# keyboard.net
KiCad netlist of a schematic drawn in EAGLE
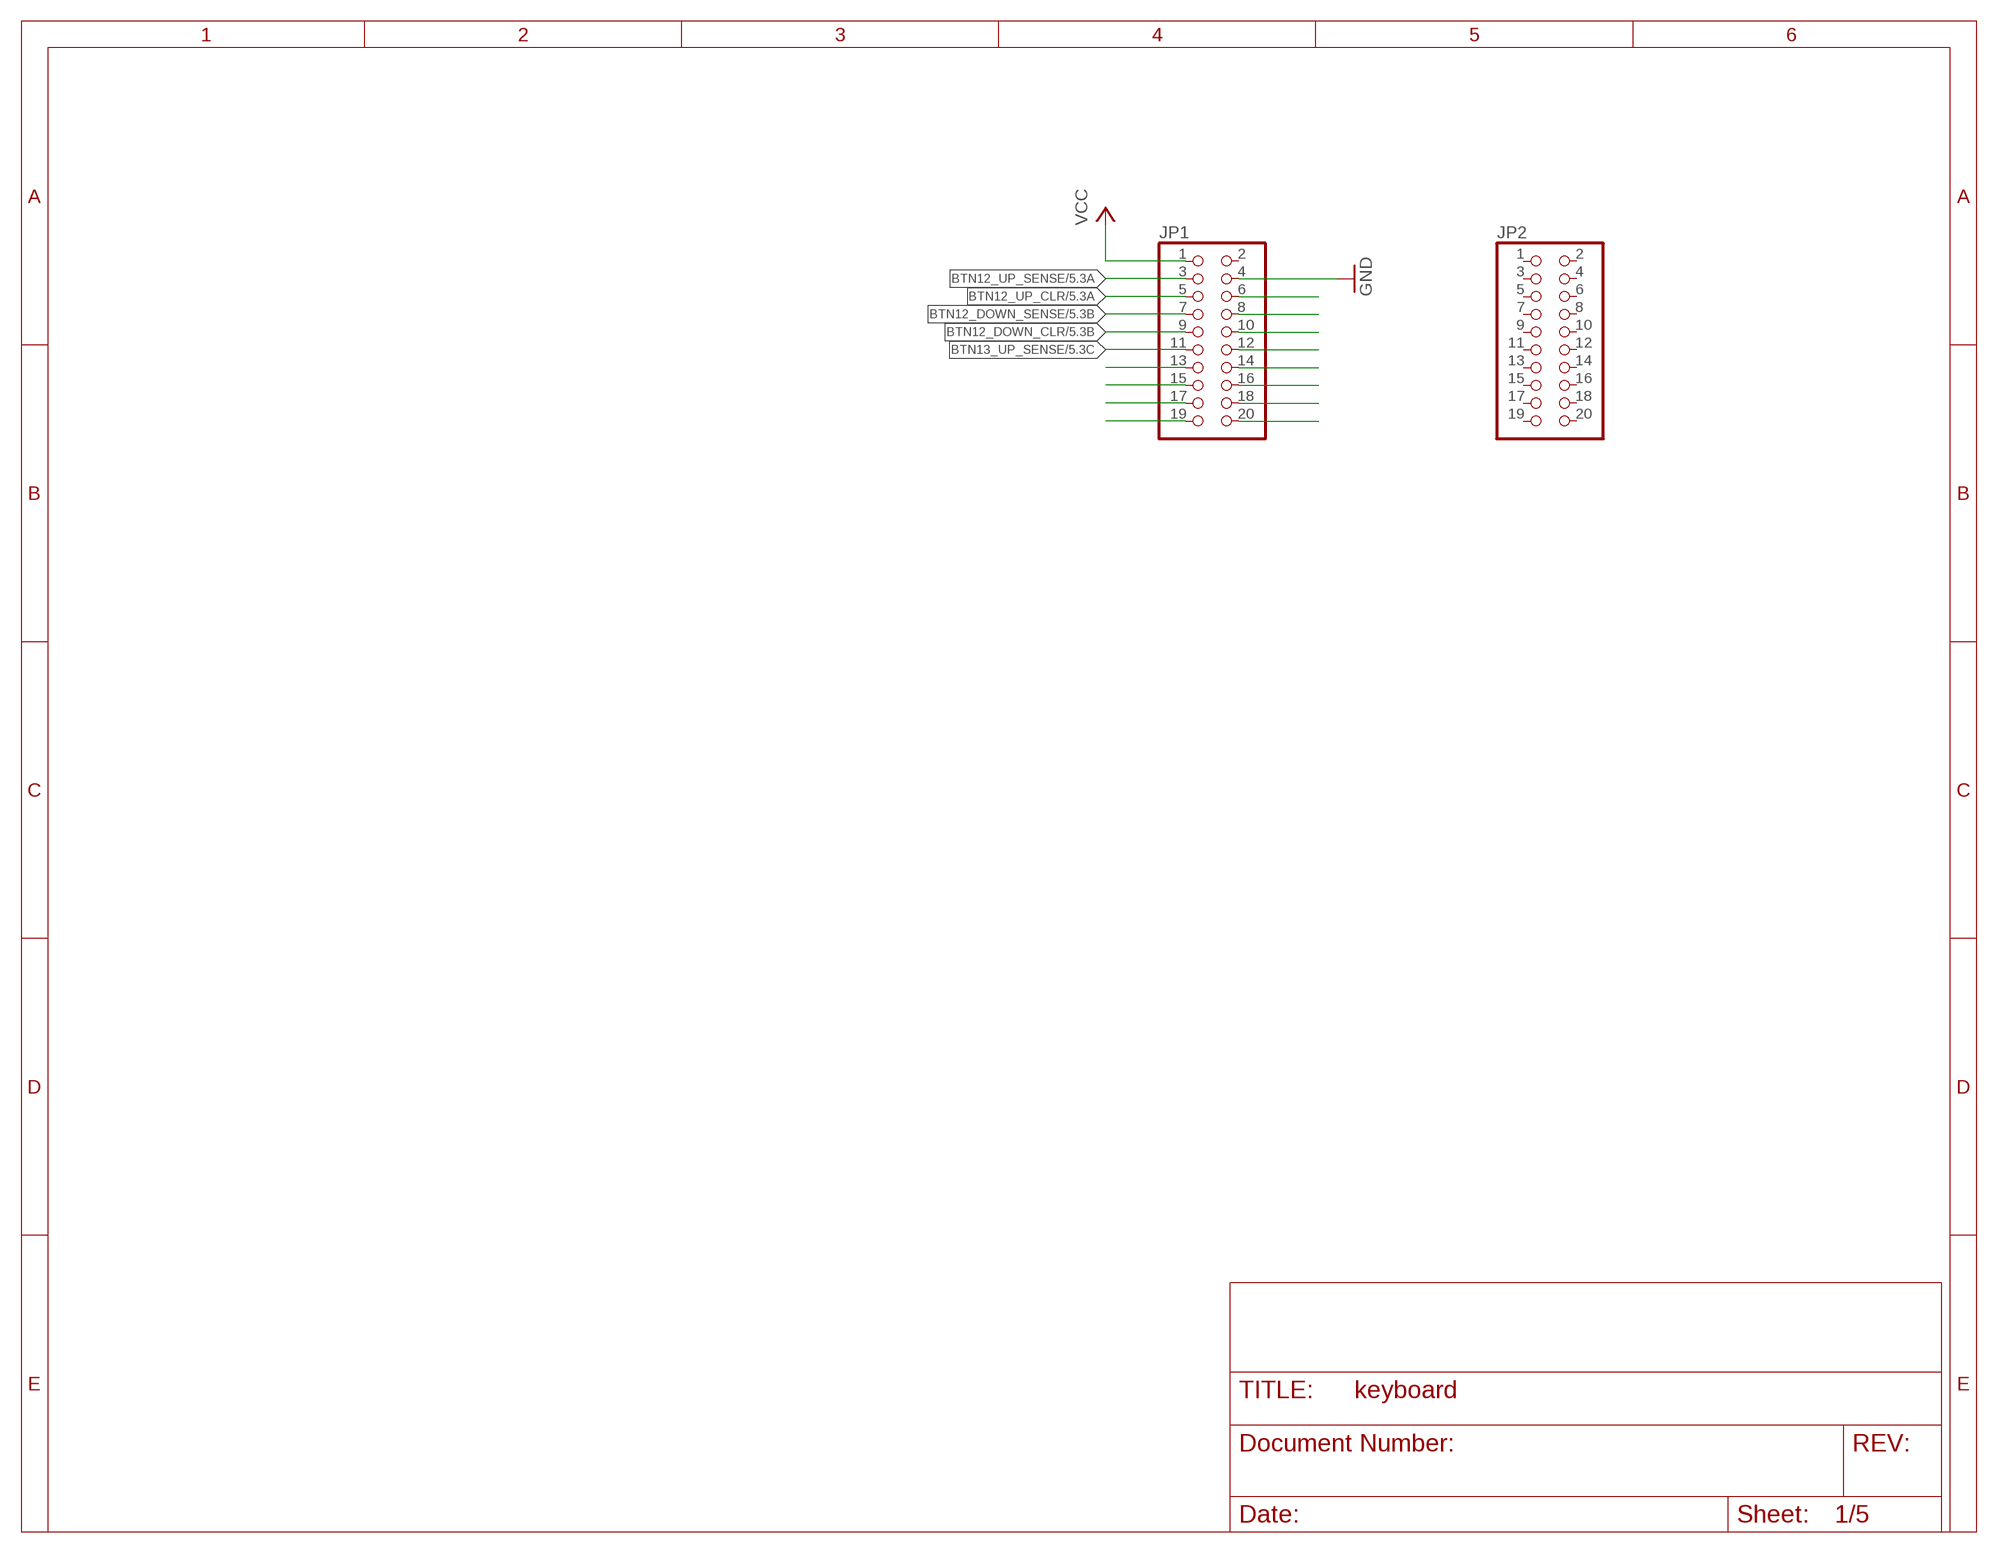
[diagram p0: schematic, sheet 1]
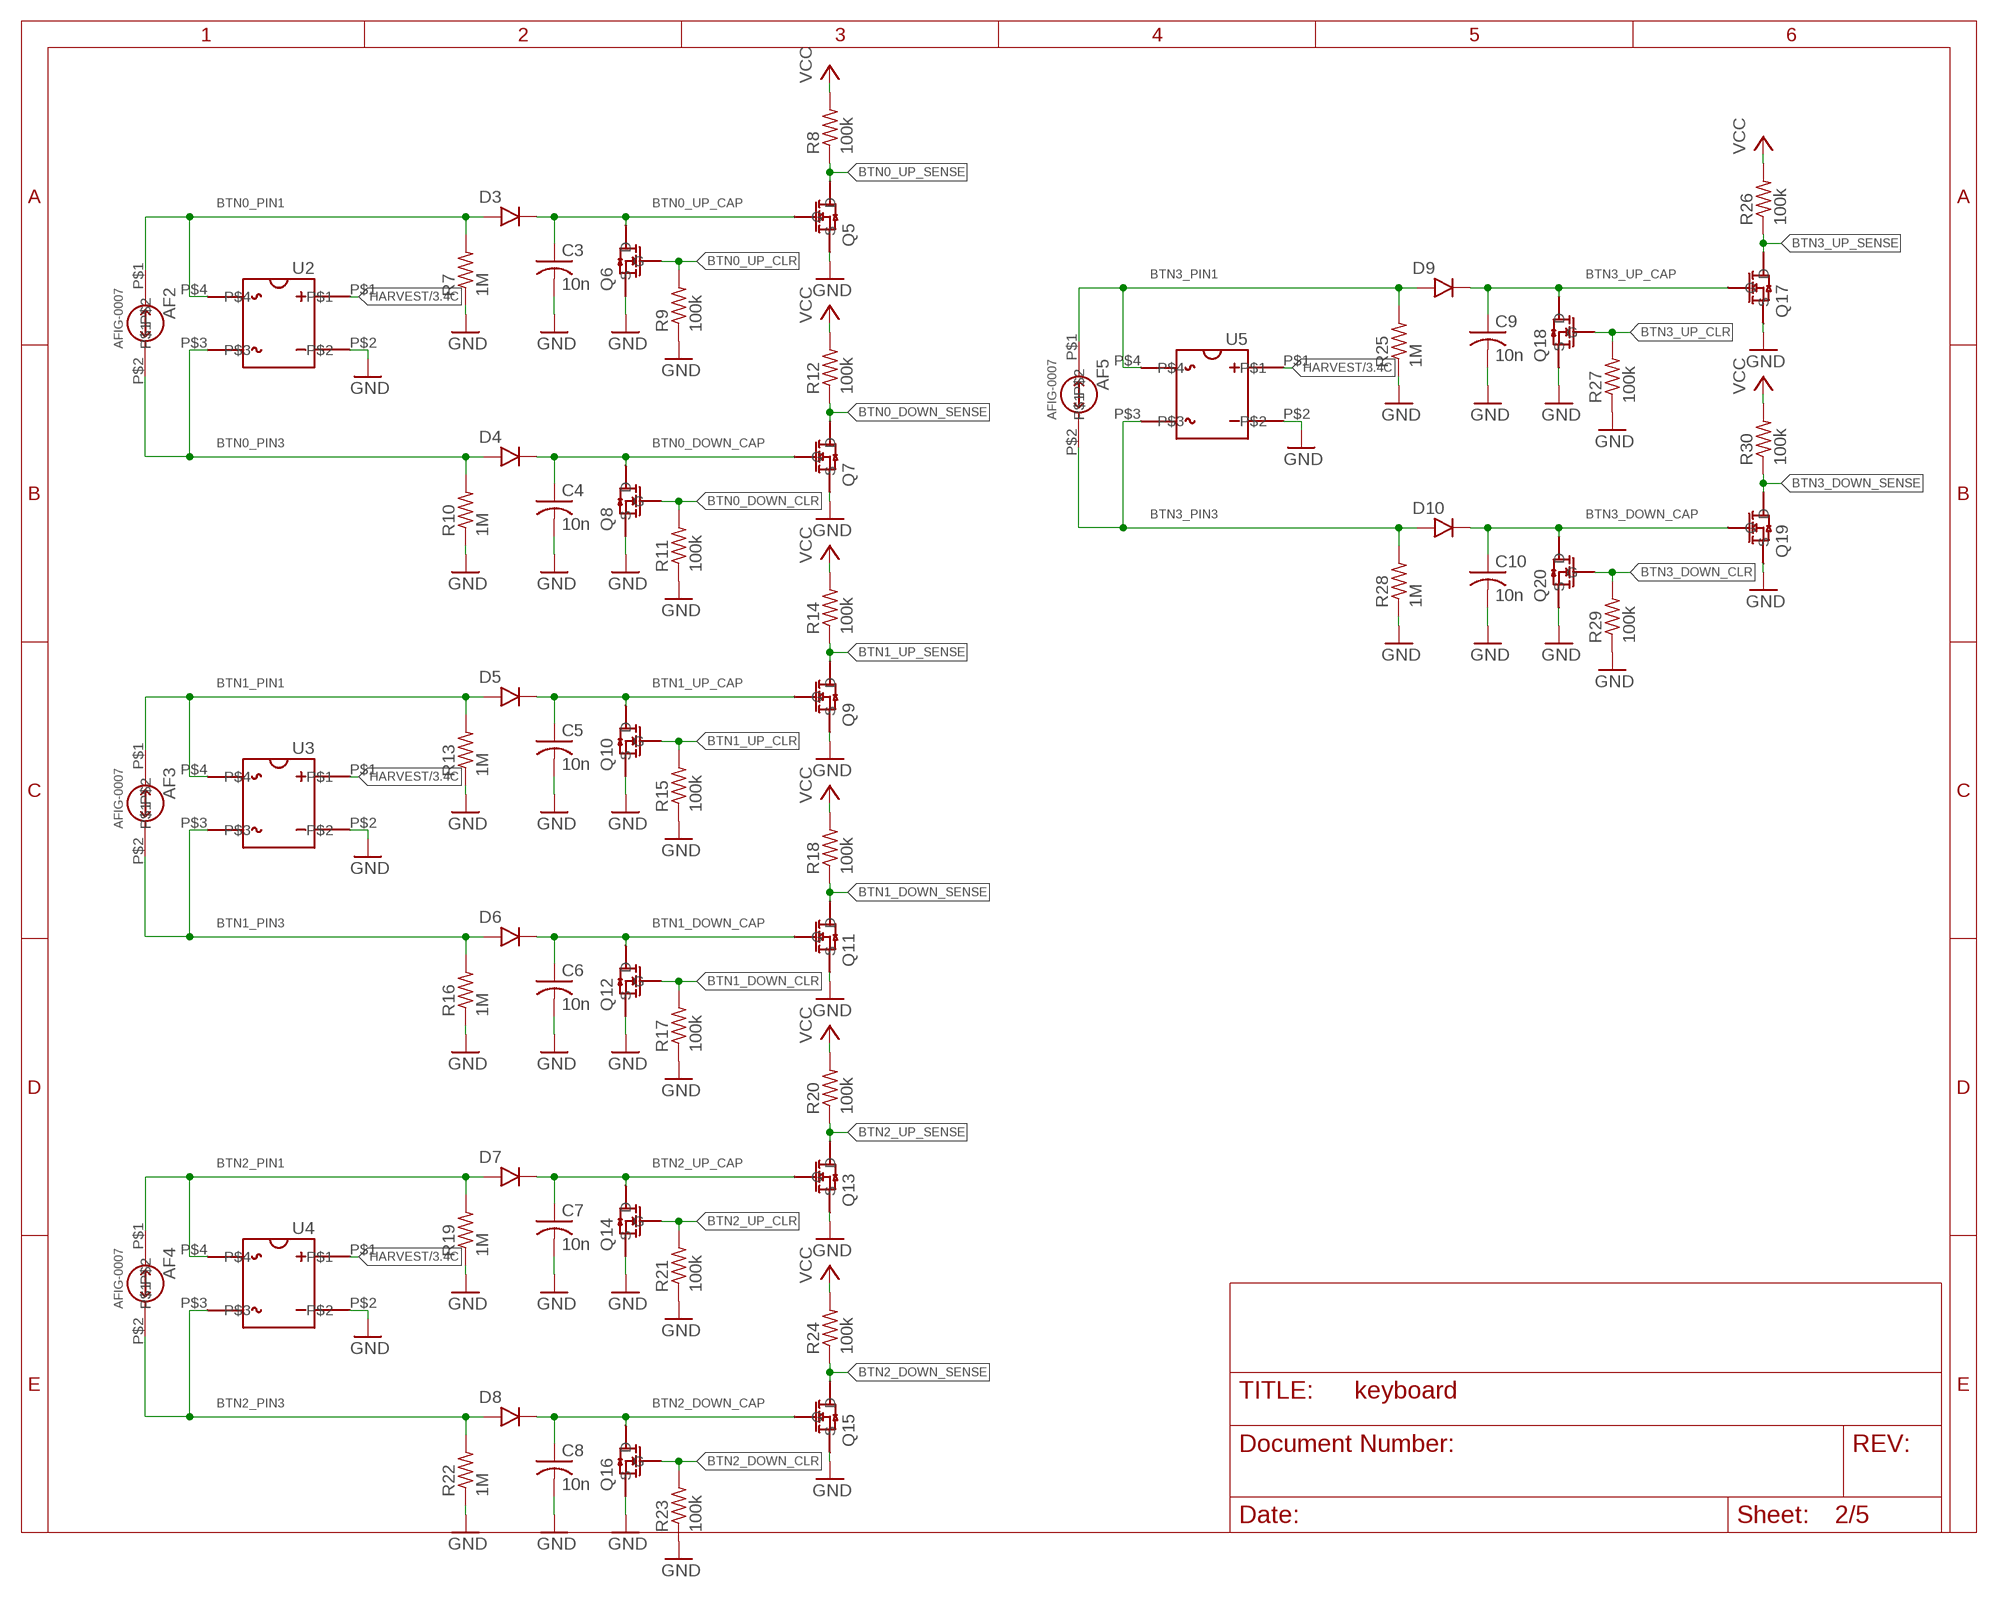
[diagram p1: schematic, sheet 2]
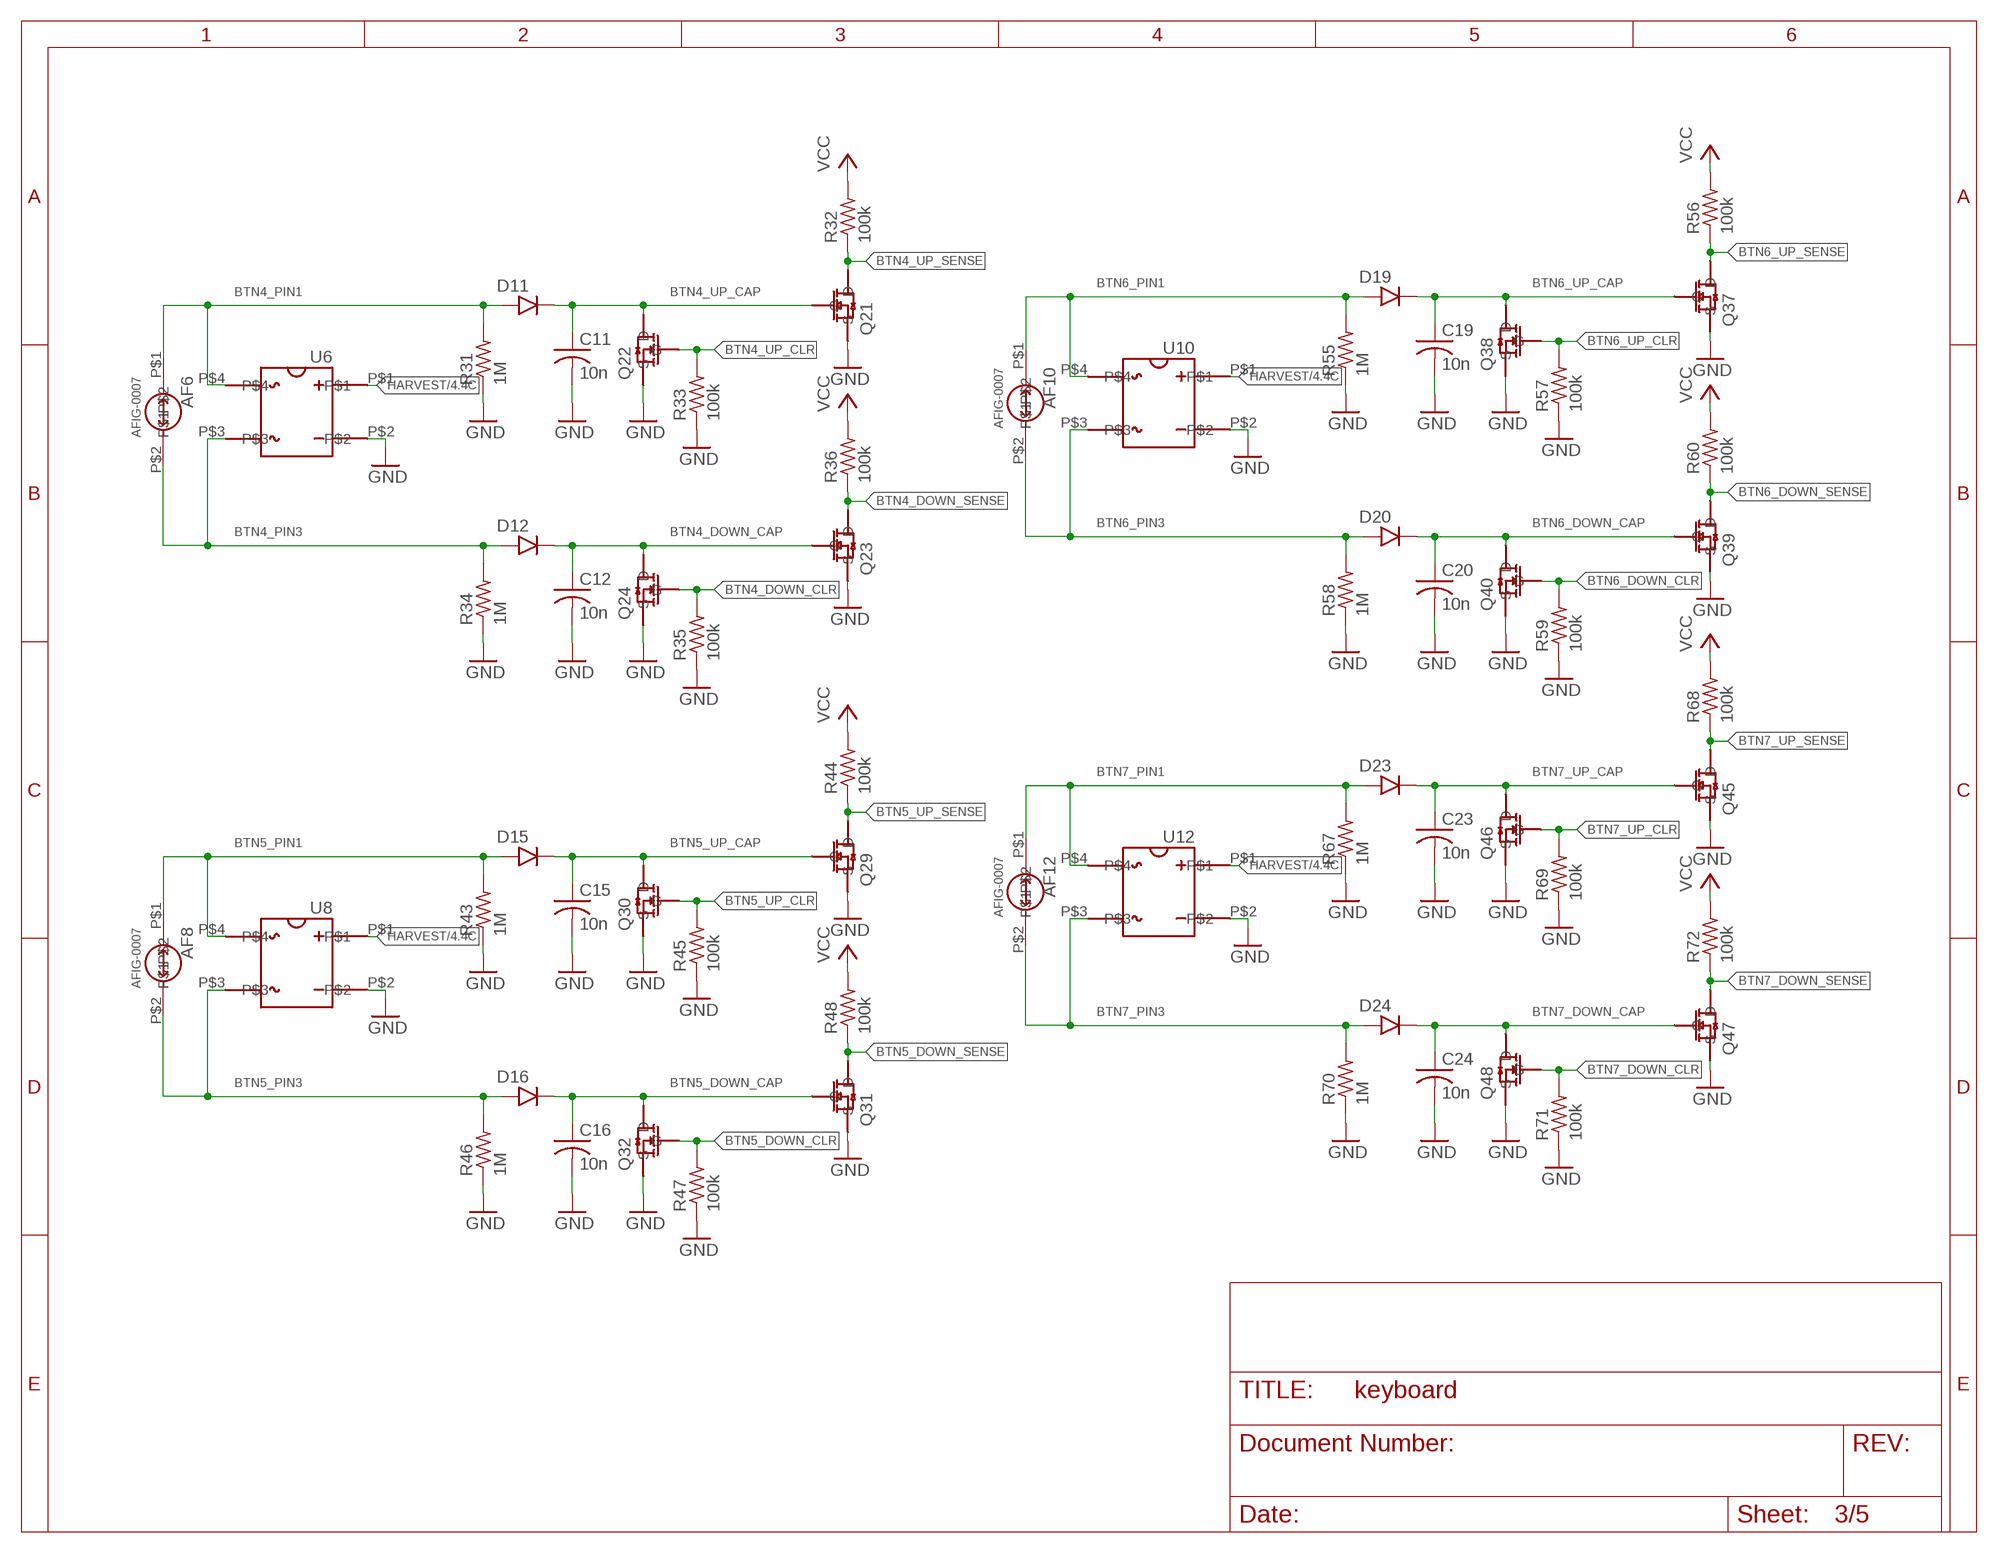
[diagram p2: schematic, sheet 3]
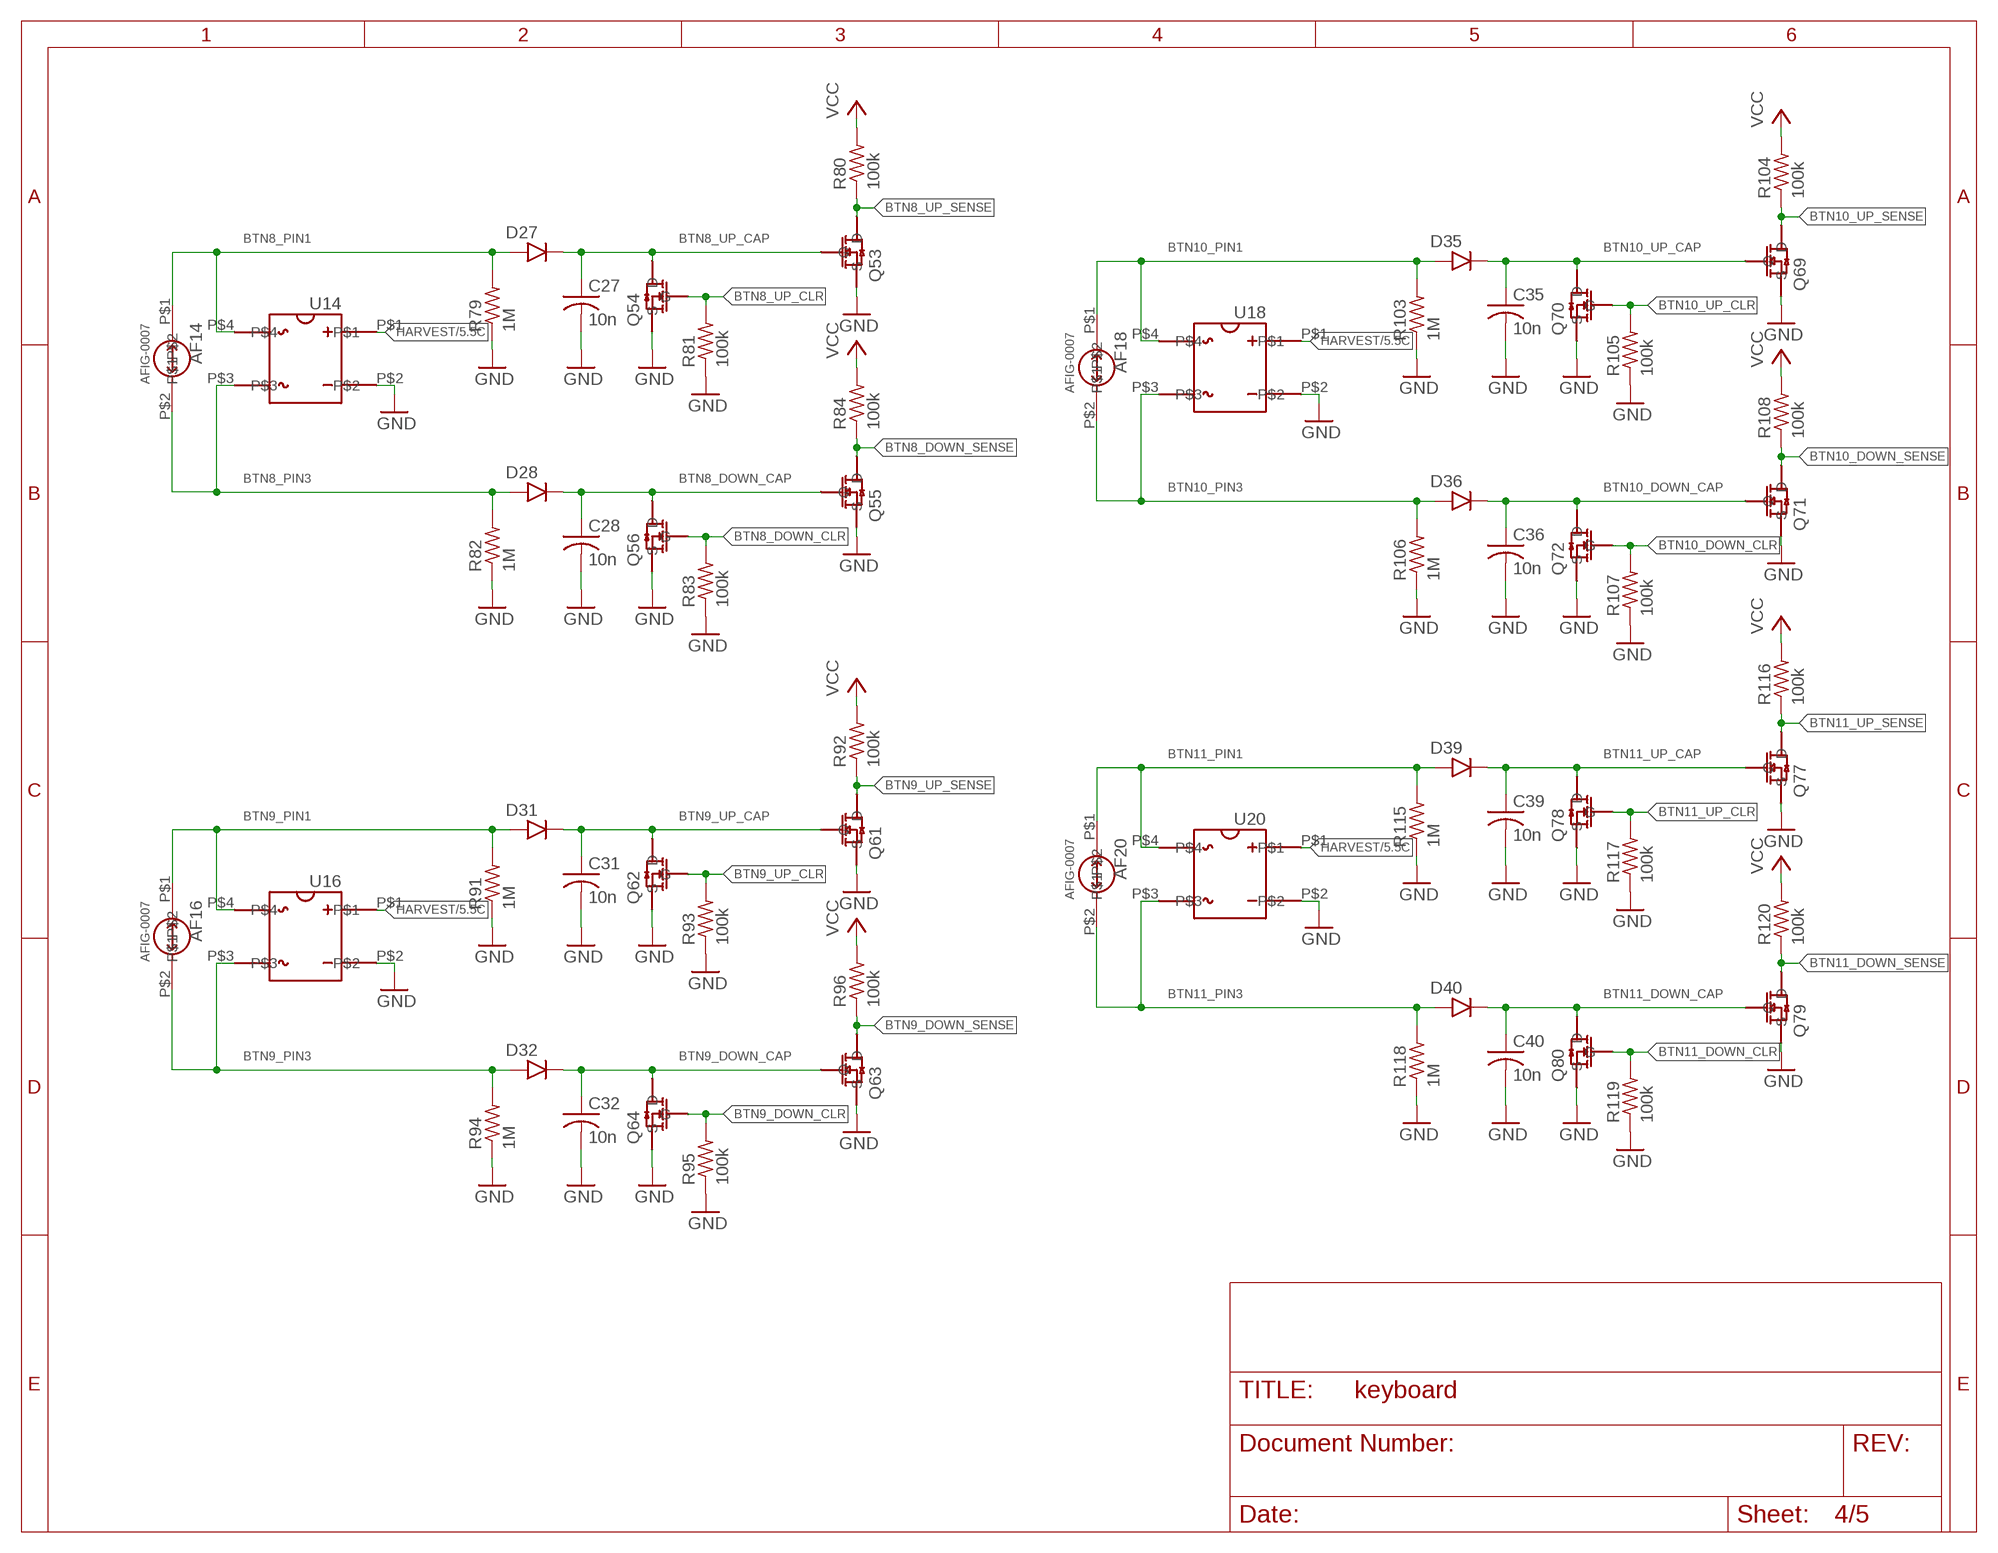
[diagram p3: schematic, sheet 4]
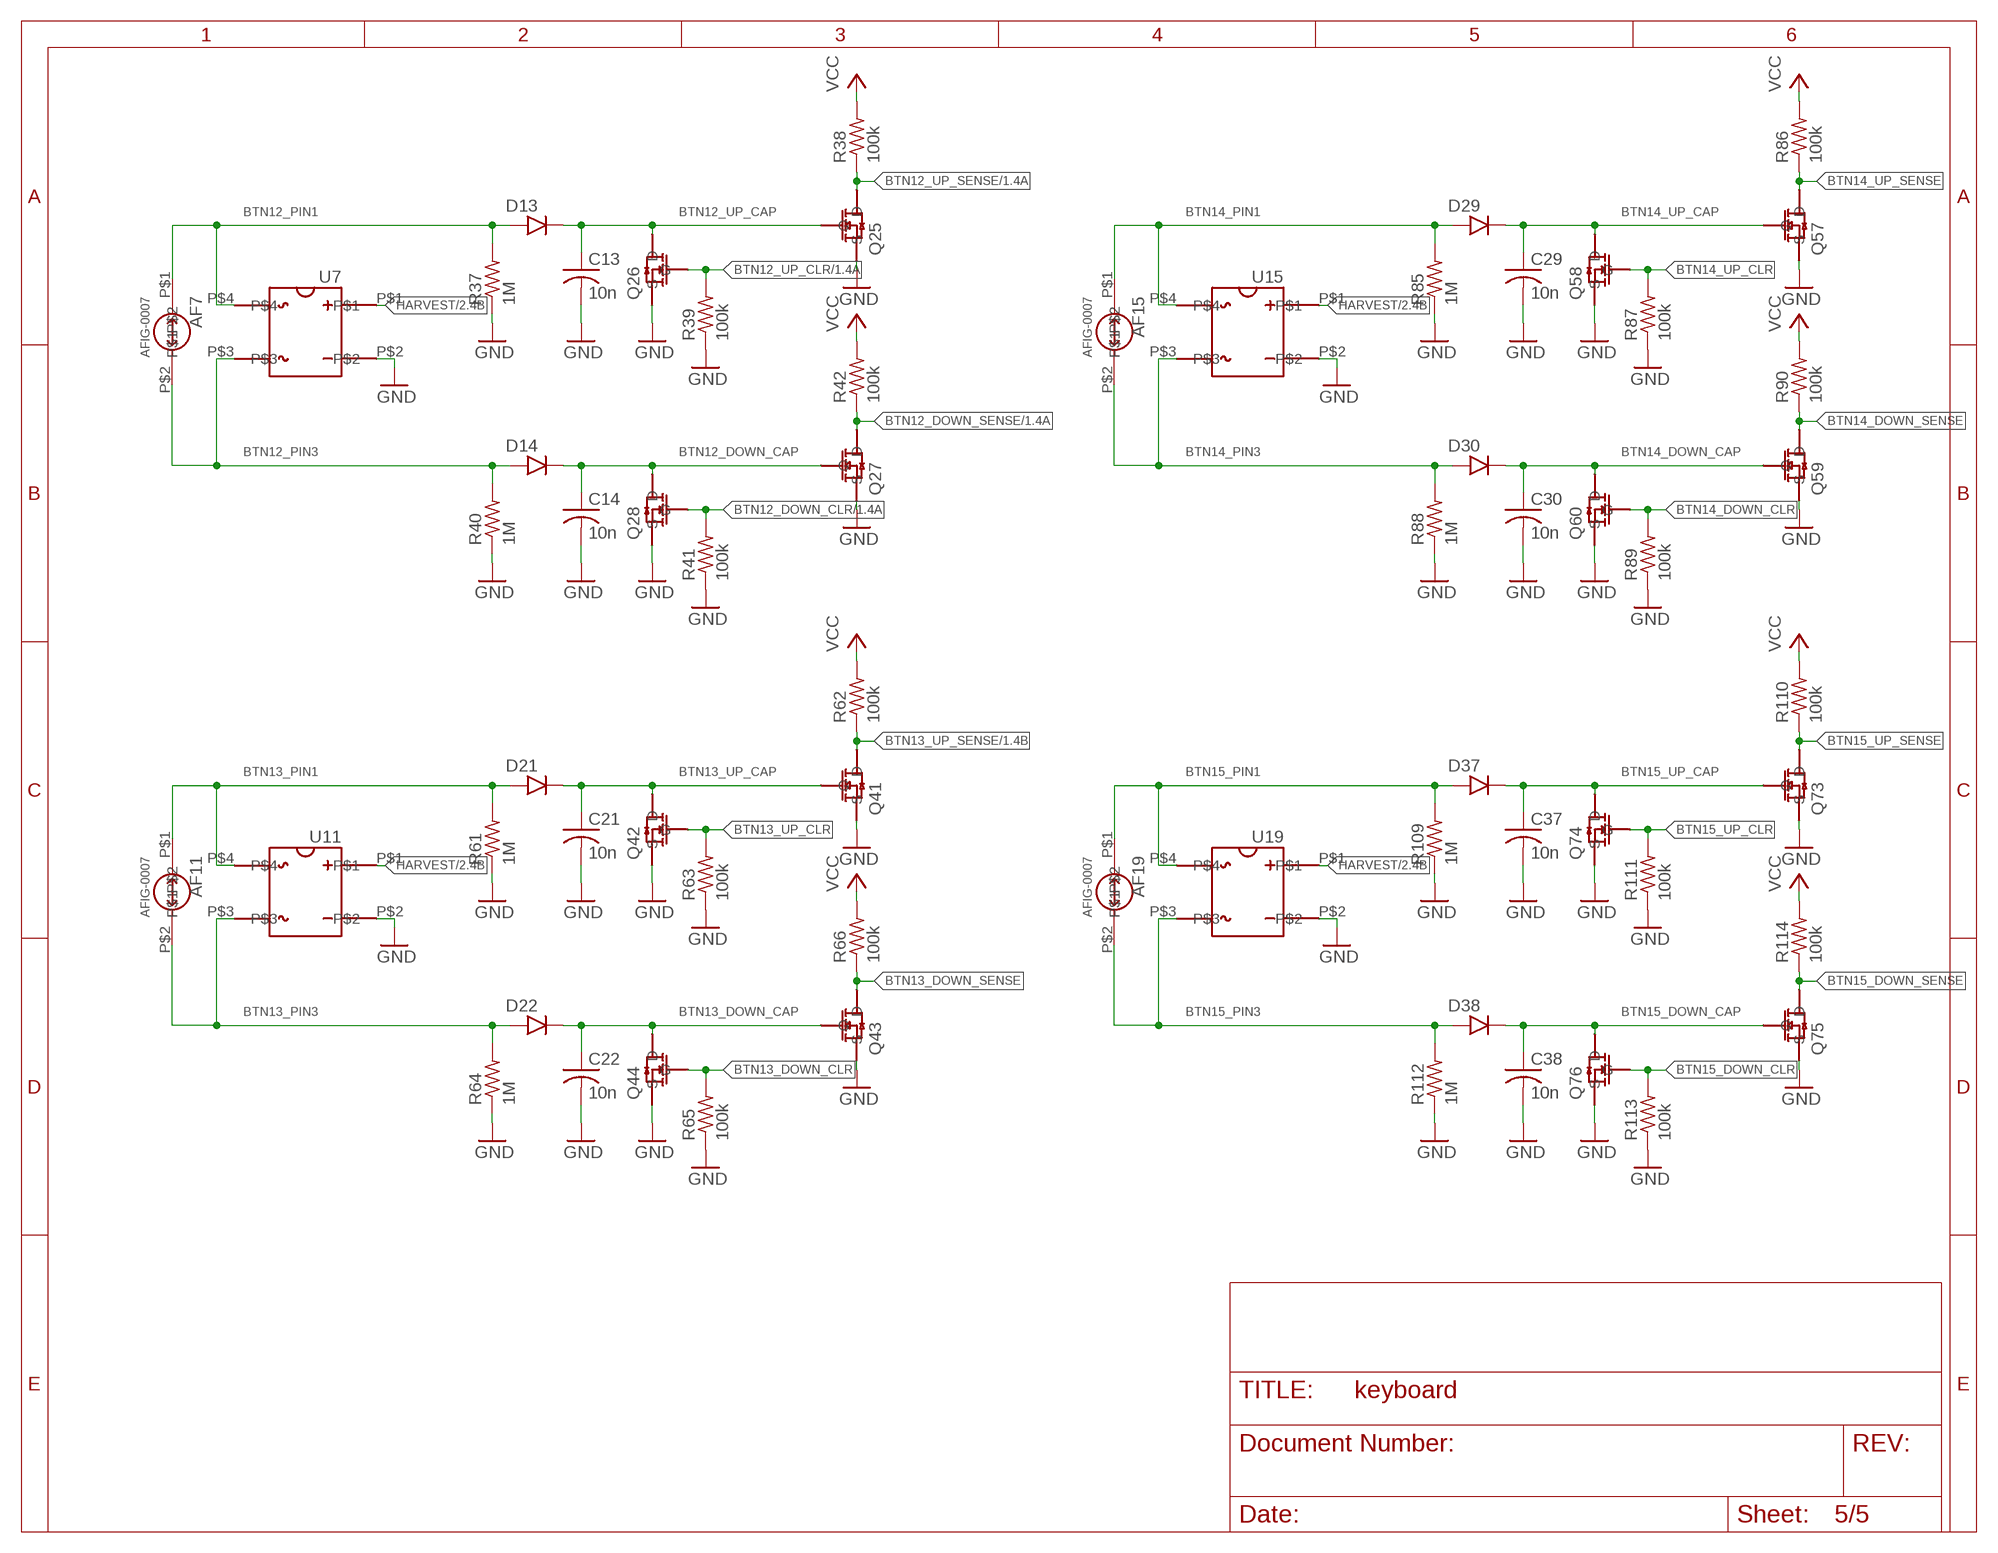
[diagram p4: schematic, sheet 5]

(export (version "E")
  (design (tool "Eeschema 10.0.6"))
  (components
    (comp (ref "JP1")
      (value "PINHD-2X10")
      (footprint "eagle-import:2X10")
      (libsource (lib "eagle-import") (part "PINHD-2X10"))
    )
    (comp (ref "JP2")
      (value "PINHD-2X10")
      (footprint "eagle-import:2X10")
      (libsource (lib "eagle-import") (part "PINHD-2X10"))
    )
    (comp (ref "AF7")
      (value "BUTTON-MOUNT")
      (footprint "eagle-import:BUTTON-MOUNT")
      (libsource (lib "eagle-import") (part "BUTTON-MOUNT"))
    )
    (comp (ref "AF11")
      (value "BUTTON-MOUNT")
      (footprint "eagle-import:BUTTON-MOUNT")
      (libsource (lib "eagle-import") (part "BUTTON-MOUNT"))
    )
    (comp (ref "AF15")
      (value "BUTTON-MOUNT")
      (footprint "eagle-import:BUTTON-MOUNT")
      (libsource (lib "eagle-import") (part "BUTTON-MOUNT"))
    )
    (comp (ref "AF19")
      (value "BUTTON-MOUNT")
      (footprint "eagle-import:BUTTON-MOUNT")
      (libsource (lib "eagle-import") (part "BUTTON-MOUNT"))
    )
    (comp (ref "C13")
      (value "10n")
      (footprint "eagle-import:C0402")
      (libsource (lib "eagle-import") (part "C-USC0402"))
    )
    (comp (ref "C14")
      (value "10n")
      (footprint "eagle-import:C0402")
      (libsource (lib "eagle-import") (part "C-USC0402"))
    )
    (comp (ref "C21")
      (value "10n")
      (footprint "eagle-import:C0402")
      (libsource (lib "eagle-import") (part "C-USC0402"))
    )
    (comp (ref "C22")
      (value "10n")
      (footprint "eagle-import:C0402")
      (libsource (lib "eagle-import") (part "C-USC0402"))
    )
    (comp (ref "C29")
      (value "10n")
      (footprint "eagle-import:C0402")
      (libsource (lib "eagle-import") (part "C-USC0402"))
    )
    (comp (ref "C30")
      (value "10n")
      (footprint "eagle-import:C0402")
      (libsource (lib "eagle-import") (part "C-USC0402"))
    )
    (comp (ref "C37")
      (value "10n")
      (footprint "eagle-import:C0402")
      (libsource (lib "eagle-import") (part "C-USC0402"))
    )
    (comp (ref "C38")
      (value "10n")
      (footprint "eagle-import:C0402")
      (libsource (lib "eagle-import") (part "C-USC0402"))
    )
    (comp (ref "D13")
      (value "DFLU1200")
      (footprint "eagle-import:DFLU1200")
      (libsource (lib "eagle-import") (part "DFLU1200"))
    )
    (comp (ref "D14")
      (value "DFLU1200")
      (footprint "eagle-import:DFLU1200")
      (libsource (lib "eagle-import") (part "DFLU1200"))
    )
    (comp (ref "D21")
      (value "DFLU1200")
      (footprint "eagle-import:DFLU1200")
      (libsource (lib "eagle-import") (part "DFLU1200"))
    )
    (comp (ref "D22")
      (value "DFLU1200")
      (footprint "eagle-import:DFLU1200")
      (libsource (lib "eagle-import") (part "DFLU1200"))
    )
    (comp (ref "D29")
      (value "DFLU1200")
      (footprint "eagle-import:DFLU1200")
      (libsource (lib "eagle-import") (part "DFLU1200"))
    )
    (comp (ref "D30")
      (value "DFLU1200")
      (footprint "eagle-import:DFLU1200")
      (libsource (lib "eagle-import") (part "DFLU1200"))
    )
    (comp (ref "D37")
      (value "DFLU1200")
      (footprint "eagle-import:DFLU1200")
      (libsource (lib "eagle-import") (part "DFLU1200"))
    )
    (comp (ref "D38")
      (value "DFLU1200")
      (footprint "eagle-import:DFLU1200")
      (libsource (lib "eagle-import") (part "DFLU1200"))
    )
    (comp (ref "Q25")
      (value "2N7002K-7")
      (footprint "eagle-import:2N7002K-7")
      (libsource (lib "eagle-import") (part "2N7002K-7"))
    )
    (comp (ref "Q26")
      (value "BSS138K")
      (footprint "eagle-import:BSS138K")
      (libsource (lib "eagle-import") (part "BSS138K"))
    )
    (comp (ref "Q27")
      (value "2N7002K-7")
      (footprint "eagle-import:2N7002K-7")
      (libsource (lib "eagle-import") (part "2N7002K-7"))
    )
    (comp (ref "Q28")
      (value "BSS138K")
      (footprint "eagle-import:BSS138K")
      (libsource (lib "eagle-import") (part "BSS138K"))
    )
    (comp (ref "Q41")
      (value "2N7002K-7")
      (footprint "eagle-import:2N7002K-7")
      (libsource (lib "eagle-import") (part "2N7002K-7"))
    )
    (comp (ref "Q42")
      (value "BSS138K")
      (footprint "eagle-import:BSS138K")
      (libsource (lib "eagle-import") (part "BSS138K"))
    )
    (comp (ref "Q43")
      (value "2N7002K-7")
      (footprint "eagle-import:2N7002K-7")
      (libsource (lib "eagle-import") (part "2N7002K-7"))
    )
    (comp (ref "Q44")
      (value "BSS138K")
      (footprint "eagle-import:BSS138K")
      (libsource (lib "eagle-import") (part "BSS138K"))
    )
    (comp (ref "Q57")
      (value "2N7002K-7")
      (footprint "eagle-import:2N7002K-7")
      (libsource (lib "eagle-import") (part "2N7002K-7"))
    )
    (comp (ref "Q58")
      (value "BSS138K")
      (footprint "eagle-import:BSS138K")
      (libsource (lib "eagle-import") (part "BSS138K"))
    )
    (comp (ref "Q59")
      (value "2N7002K-7")
      (footprint "eagle-import:2N7002K-7")
      (libsource (lib "eagle-import") (part "2N7002K-7"))
    )
    (comp (ref "Q60")
      (value "BSS138K")
      (footprint "eagle-import:BSS138K")
      (libsource (lib "eagle-import") (part "BSS138K"))
    )
    (comp (ref "Q73")
      (value "2N7002K-7")
      (footprint "eagle-import:2N7002K-7")
      (libsource (lib "eagle-import") (part "2N7002K-7"))
    )
    (comp (ref "Q74")
      (value "BSS138K")
      (footprint "eagle-import:BSS138K")
      (libsource (lib "eagle-import") (part "BSS138K"))
    )
    (comp (ref "Q75")
      (value "2N7002K-7")
      (footprint "eagle-import:2N7002K-7")
      (libsource (lib "eagle-import") (part "2N7002K-7"))
    )
    (comp (ref "Q76")
      (value "BSS138K")
      (footprint "eagle-import:BSS138K")
      (libsource (lib "eagle-import") (part "BSS138K"))
    )
    (comp (ref "R37")
      (value "1M")
      (footprint "eagle-import:R0402")
      (libsource (lib "eagle-import") (part "R-US_R0402"))
    )
    (comp (ref "R38")
      (value "100k")
      (footprint "eagle-import:R0402")
      (libsource (lib "eagle-import") (part "R-US_R0402"))
    )
    (comp (ref "R39")
      (value "100k")
      (footprint "eagle-import:R0402")
      (libsource (lib "eagle-import") (part "R-US_R0402"))
    )
    (comp (ref "R40")
      (value "1M")
      (footprint "eagle-import:R0402")
      (libsource (lib "eagle-import") (part "R-US_R0402"))
    )
    (comp (ref "R41")
      (value "100k")
      (footprint "eagle-import:R0402")
      (libsource (lib "eagle-import") (part "R-US_R0402"))
    )
    (comp (ref "R42")
      (value "100k")
      (footprint "eagle-import:R0402")
      (libsource (lib "eagle-import") (part "R-US_R0402"))
    )
    (comp (ref "R61")
      (value "1M")
      (footprint "eagle-import:R0402")
      (libsource (lib "eagle-import") (part "R-US_R0402"))
    )
    (comp (ref "R62")
      (value "100k")
      (footprint "eagle-import:R0402")
      (libsource (lib "eagle-import") (part "R-US_R0402"))
    )
    (comp (ref "R63")
      (value "100k")
      (footprint "eagle-import:R0402")
      (libsource (lib "eagle-import") (part "R-US_R0402"))
    )
    (comp (ref "R64")
      (value "1M")
      (footprint "eagle-import:R0402")
      (libsource (lib "eagle-import") (part "R-US_R0402"))
    )
    (comp (ref "R65")
      (value "100k")
      (footprint "eagle-import:R0402")
      (libsource (lib "eagle-import") (part "R-US_R0402"))
    )
    (comp (ref "R66")
      (value "100k")
      (footprint "eagle-import:R0402")
      (libsource (lib "eagle-import") (part "R-US_R0402"))
    )
    (comp (ref "R85")
      (value "1M")
      (footprint "eagle-import:R0402")
      (libsource (lib "eagle-import") (part "R-US_R0402"))
    )
    (comp (ref "R86")
      (value "100k")
      (footprint "eagle-import:R0402")
      (libsource (lib "eagle-import") (part "R-US_R0402"))
    )
    (comp (ref "R87")
      (value "100k")
      (footprint "eagle-import:R0402")
      (libsource (lib "eagle-import") (part "R-US_R0402"))
    )
    (comp (ref "R88")
      (value "1M")
      (footprint "eagle-import:R0402")
      (libsource (lib "eagle-import") (part "R-US_R0402"))
    )
    (comp (ref "R89")
      (value "100k")
      (footprint "eagle-import:R0402")
      (libsource (lib "eagle-import") (part "R-US_R0402"))
    )
    (comp (ref "R90")
      (value "100k")
      (footprint "eagle-import:R0402")
      (libsource (lib "eagle-import") (part "R-US_R0402"))
    )
    (comp (ref "R109")
      (value "1M")
      (footprint "eagle-import:R0402")
      (libsource (lib "eagle-import") (part "R-US_R0402"))
    )
    (comp (ref "R110")
      (value "100k")
      (footprint "eagle-import:R0402")
      (libsource (lib "eagle-import") (part "R-US_R0402"))
    )
    (comp (ref "R111")
      (value "100k")
      (footprint "eagle-import:R0402")
      (libsource (lib "eagle-import") (part "R-US_R0402"))
    )
    (comp (ref "R112")
      (value "1M")
      (footprint "eagle-import:R0402")
      (libsource (lib "eagle-import") (part "R-US_R0402"))
    )
    (comp (ref "R113")
      (value "100k")
      (footprint "eagle-import:R0402")
      (libsource (lib "eagle-import") (part "R-US_R0402"))
    )
    (comp (ref "R114")
      (value "100k")
      (footprint "eagle-import:R0402")
      (libsource (lib "eagle-import") (part "R-US_R0402"))
    )
    (comp (ref "U7")
      (value "CDBHD140L-G")
      (footprint "eagle-import:CDBHDXX0L-G")
      (libsource (lib "eagle-import") (part "CDBHD140L-G"))
    )
    (comp (ref "U11")
      (value "CDBHD140L-G")
      (footprint "eagle-import:CDBHDXX0L-G")
      (libsource (lib "eagle-import") (part "CDBHD140L-G"))
    )
    (comp (ref "U15")
      (value "CDBHD140L-G")
      (footprint "eagle-import:CDBHDXX0L-G")
      (libsource (lib "eagle-import") (part "CDBHD140L-G"))
    )
    (comp (ref "U19")
      (value "CDBHD140L-G")
      (footprint "eagle-import:CDBHDXX0L-G")
      (libsource (lib "eagle-import") (part "CDBHD140L-G"))
    )
    (comp (ref "AF6")
      (value "BUTTON-MOUNT")
      (footprint "eagle-import:BUTTON-MOUNT")
      (libsource (lib "eagle-import") (part "BUTTON-MOUNT"))
    )
    (comp (ref "AF8")
      (value "BUTTON-MOUNT")
      (footprint "eagle-import:BUTTON-MOUNT")
      (libsource (lib "eagle-import") (part "BUTTON-MOUNT"))
    )
    (comp (ref "AF10")
      (value "BUTTON-MOUNT")
      (footprint "eagle-import:BUTTON-MOUNT")
      (libsource (lib "eagle-import") (part "BUTTON-MOUNT"))
    )
    (comp (ref "AF12")
      (value "BUTTON-MOUNT")
      (footprint "eagle-import:BUTTON-MOUNT")
      (libsource (lib "eagle-import") (part "BUTTON-MOUNT"))
    )
    (comp (ref "C11")
      (value "10n")
      (footprint "eagle-import:C0402")
      (libsource (lib "eagle-import") (part "C-USC0402"))
    )
    (comp (ref "C12")
      (value "10n")
      (footprint "eagle-import:C0402")
      (libsource (lib "eagle-import") (part "C-USC0402"))
    )
    (comp (ref "C15")
      (value "10n")
      (footprint "eagle-import:C0402")
      (libsource (lib "eagle-import") (part "C-USC0402"))
    )
    (comp (ref "C16")
      (value "10n")
      (footprint "eagle-import:C0402")
      (libsource (lib "eagle-import") (part "C-USC0402"))
    )
    (comp (ref "C19")
      (value "10n")
      (footprint "eagle-import:C0402")
      (libsource (lib "eagle-import") (part "C-USC0402"))
    )
    (comp (ref "C20")
      (value "10n")
      (footprint "eagle-import:C0402")
      (libsource (lib "eagle-import") (part "C-USC0402"))
    )
    (comp (ref "C23")
      (value "10n")
      (footprint "eagle-import:C0402")
      (libsource (lib "eagle-import") (part "C-USC0402"))
    )
    (comp (ref "C24")
      (value "10n")
      (footprint "eagle-import:C0402")
      (libsource (lib "eagle-import") (part "C-USC0402"))
    )
    (comp (ref "D11")
      (value "DFLU1200")
      (footprint "eagle-import:DFLU1200")
      (libsource (lib "eagle-import") (part "DFLU1200"))
    )
    (comp (ref "D12")
      (value "DFLU1200")
      (footprint "eagle-import:DFLU1200")
      (libsource (lib "eagle-import") (part "DFLU1200"))
    )
    (comp (ref "D15")
      (value "DFLU1200")
      (footprint "eagle-import:DFLU1200")
      (libsource (lib "eagle-import") (part "DFLU1200"))
    )
    (comp (ref "D16")
      (value "DFLU1200")
      (footprint "eagle-import:DFLU1200")
      (libsource (lib "eagle-import") (part "DFLU1200"))
    )
    (comp (ref "D19")
      (value "DFLU1200")
      (footprint "eagle-import:DFLU1200")
      (libsource (lib "eagle-import") (part "DFLU1200"))
    )
    (comp (ref "D20")
      (value "DFLU1200")
      (footprint "eagle-import:DFLU1200")
      (libsource (lib "eagle-import") (part "DFLU1200"))
    )
    (comp (ref "D23")
      (value "DFLU1200")
      (footprint "eagle-import:DFLU1200")
      (libsource (lib "eagle-import") (part "DFLU1200"))
    )
    (comp (ref "D24")
      (value "DFLU1200")
      (footprint "eagle-import:DFLU1200")
      (libsource (lib "eagle-import") (part "DFLU1200"))
    )
    (comp (ref "Q21")
      (value "2N7002K-7")
      (footprint "eagle-import:2N7002K-7")
      (libsource (lib "eagle-import") (part "2N7002K-7"))
    )
    (comp (ref "Q22")
      (value "BSS138K")
      (footprint "eagle-import:BSS138K")
      (libsource (lib "eagle-import") (part "BSS138K"))
    )
    (comp (ref "Q23")
      (value "2N7002K-7")
      (footprint "eagle-import:2N7002K-7")
      (libsource (lib "eagle-import") (part "2N7002K-7"))
    )
    (comp (ref "Q24")
      (value "BSS138K")
      (footprint "eagle-import:BSS138K")
      (libsource (lib "eagle-import") (part "BSS138K"))
    )
    (comp (ref "Q29")
      (value "2N7002K-7")
      (footprint "eagle-import:2N7002K-7")
      (libsource (lib "eagle-import") (part "2N7002K-7"))
    )
    (comp (ref "Q30")
      (value "BSS138K")
      (footprint "eagle-import:BSS138K")
      (libsource (lib "eagle-import") (part "BSS138K"))
    )
    (comp (ref "Q31")
      (value "2N7002K-7")
      (footprint "eagle-import:2N7002K-7")
      (libsource (lib "eagle-import") (part "2N7002K-7"))
    )
    (comp (ref "Q32")
      (value "BSS138K")
      (footprint "eagle-import:BSS138K")
      (libsource (lib "eagle-import") (part "BSS138K"))
    )
    (comp (ref "Q37")
      (value "2N7002K-7")
      (footprint "eagle-import:2N7002K-7")
      (libsource (lib "eagle-import") (part "2N7002K-7"))
    )
    (comp (ref "Q38")
      (value "BSS138K")
      (footprint "eagle-import:BSS138K")
      (libsource (lib "eagle-import") (part "BSS138K"))
    )
    (comp (ref "Q39")
      (value "2N7002K-7")
      (footprint "eagle-import:2N7002K-7")
      (libsource (lib "eagle-import") (part "2N7002K-7"))
    )
    (comp (ref "Q40")
      (value "BSS138K")
      (footprint "eagle-import:BSS138K")
      (libsource (lib "eagle-import") (part "BSS138K"))
    )
    (comp (ref "Q45")
      (value "2N7002K-7")
      (footprint "eagle-import:2N7002K-7")
      (libsource (lib "eagle-import") (part "2N7002K-7"))
    )
    (comp (ref "Q46")
      (value "BSS138K")
      (footprint "eagle-import:BSS138K")
      (libsource (lib "eagle-import") (part "BSS138K"))
    )
    (comp (ref "Q47")
      (value "2N7002K-7")
      (footprint "eagle-import:2N7002K-7")
      (libsource (lib "eagle-import") (part "2N7002K-7"))
    )
    (comp (ref "Q48")
      (value "BSS138K")
      (footprint "eagle-import:BSS138K")
      (libsource (lib "eagle-import") (part "BSS138K"))
    )
    (comp (ref "R31")
      (value "1M")
      (footprint "eagle-import:R0402")
      (libsource (lib "eagle-import") (part "R-US_R0402"))
    )
    (comp (ref "R32")
      (value "100k")
      (footprint "eagle-import:R0402")
      (libsource (lib "eagle-import") (part "R-US_R0402"))
    )
    (comp (ref "R33")
      (value "100k")
      (footprint "eagle-import:R0402")
      (libsource (lib "eagle-import") (part "R-US_R0402"))
    )
    (comp (ref "R34")
      (value "1M")
      (footprint "eagle-import:R0402")
      (libsource (lib "eagle-import") (part "R-US_R0402"))
    )
    (comp (ref "R35")
      (value "100k")
      (footprint "eagle-import:R0402")
      (libsource (lib "eagle-import") (part "R-US_R0402"))
    )
    (comp (ref "R36")
      (value "100k")
      (footprint "eagle-import:R0402")
      (libsource (lib "eagle-import") (part "R-US_R0402"))
    )
    (comp (ref "R43")
      (value "1M")
      (footprint "eagle-import:R0402")
      (libsource (lib "eagle-import") (part "R-US_R0402"))
    )
    (comp (ref "R44")
      (value "100k")
      (footprint "eagle-import:R0402")
      (libsource (lib "eagle-import") (part "R-US_R0402"))
    )
    (comp (ref "R45")
      (value "100k")
      (footprint "eagle-import:R0402")
      (libsource (lib "eagle-import") (part "R-US_R0402"))
    )
    (comp (ref "R46")
      (value "1M")
      (footprint "eagle-import:R0402")
      (libsource (lib "eagle-import") (part "R-US_R0402"))
    )
    (comp (ref "R47")
      (value "100k")
      (footprint "eagle-import:R0402")
      (libsource (lib "eagle-import") (part "R-US_R0402"))
    )
    (comp (ref "R48")
      (value "100k")
      (footprint "eagle-import:R0402")
      (libsource (lib "eagle-import") (part "R-US_R0402"))
    )
    (comp (ref "R55")
      (value "1M")
      (footprint "eagle-import:R0402")
      (libsource (lib "eagle-import") (part "R-US_R0402"))
    )
    (comp (ref "R56")
      (value "100k")
      (footprint "eagle-import:R0402")
      (libsource (lib "eagle-import") (part "R-US_R0402"))
    )
    (comp (ref "R57")
      (value "100k")
      (footprint "eagle-import:R0402")
      (libsource (lib "eagle-import") (part "R-US_R0402"))
    )
    (comp (ref "R58")
      (value "1M")
      (footprint "eagle-import:R0402")
      (libsource (lib "eagle-import") (part "R-US_R0402"))
    )
    (comp (ref "R59")
      (value "100k")
      (footprint "eagle-import:R0402")
      (libsource (lib "eagle-import") (part "R-US_R0402"))
    )
    (comp (ref "R60")
      (value "100k")
      (footprint "eagle-import:R0402")
      (libsource (lib "eagle-import") (part "R-US_R0402"))
    )
    (comp (ref "R67")
      (value "1M")
      (footprint "eagle-import:R0402")
      (libsource (lib "eagle-import") (part "R-US_R0402"))
    )
    (comp (ref "R68")
      (value "100k")
      (footprint "eagle-import:R0402")
      (libsource (lib "eagle-import") (part "R-US_R0402"))
    )
    (comp (ref "R69")
      (value "100k")
      (footprint "eagle-import:R0402")
      (libsource (lib "eagle-import") (part "R-US_R0402"))
    )
    (comp (ref "R70")
      (value "1M")
      (footprint "eagle-import:R0402")
      (libsource (lib "eagle-import") (part "R-US_R0402"))
    )
    (comp (ref "R71")
      (value "100k")
      (footprint "eagle-import:R0402")
      (libsource (lib "eagle-import") (part "R-US_R0402"))
    )
    (comp (ref "R72")
      (value "100k")
      (footprint "eagle-import:R0402")
      (libsource (lib "eagle-import") (part "R-US_R0402"))
    )
    (comp (ref "U6")
      (value "CDBHD140L-G")
      (footprint "eagle-import:CDBHDXX0L-G")
      (libsource (lib "eagle-import") (part "CDBHD140L-G"))
    )
    (comp (ref "U8")
      (value "CDBHD140L-G")
      (footprint "eagle-import:CDBHDXX0L-G")
      (libsource (lib "eagle-import") (part "CDBHD140L-G"))
    )
    (comp (ref "U10")
      (value "CDBHD140L-G")
      (footprint "eagle-import:CDBHDXX0L-G")
      (libsource (lib "eagle-import") (part "CDBHD140L-G"))
    )
    (comp (ref "U12")
      (value "CDBHD140L-G")
      (footprint "eagle-import:CDBHDXX0L-G")
      (libsource (lib "eagle-import") (part "CDBHD140L-G"))
    )
    (comp (ref "AF2")
      (value "BUTTON-MOUNT")
      (footprint "eagle-import:BUTTON-MOUNT")
      (libsource (lib "eagle-import") (part "BUTTON-MOUNT"))
    )
    (comp (ref "AF3")
      (value "BUTTON-MOUNT")
      (footprint "eagle-import:BUTTON-MOUNT")
      (libsource (lib "eagle-import") (part "BUTTON-MOUNT"))
    )
    (comp (ref "AF4")
      (value "BUTTON-MOUNT")
      (footprint "eagle-import:BUTTON-MOUNT")
      (libsource (lib "eagle-import") (part "BUTTON-MOUNT"))
    )
    (comp (ref "AF5")
      (value "BUTTON-MOUNT")
      (footprint "eagle-import:BUTTON-MOUNT")
      (libsource (lib "eagle-import") (part "BUTTON-MOUNT"))
    )
    (comp (ref "C3")
      (value "10n")
      (footprint "eagle-import:C0402")
      (libsource (lib "eagle-import") (part "C-USC0402"))
    )
    (comp (ref "C4")
      (value "10n")
      (footprint "eagle-import:C0402")
      (libsource (lib "eagle-import") (part "C-USC0402"))
    )
    (comp (ref "C5")
      (value "10n")
      (footprint "eagle-import:C0402")
      (libsource (lib "eagle-import") (part "C-USC0402"))
    )
    (comp (ref "C6")
      (value "10n")
      (footprint "eagle-import:C0402")
      (libsource (lib "eagle-import") (part "C-USC0402"))
    )
    (comp (ref "C7")
      (value "10n")
      (footprint "eagle-import:C0402")
      (libsource (lib "eagle-import") (part "C-USC0402"))
    )
    (comp (ref "C8")
      (value "10n")
      (footprint "eagle-import:C0402")
      (libsource (lib "eagle-import") (part "C-USC0402"))
    )
    (comp (ref "C9")
      (value "10n")
      (footprint "eagle-import:C0402")
      (libsource (lib "eagle-import") (part "C-USC0402"))
    )
    (comp (ref "C10")
      (value "10n")
      (footprint "eagle-import:C0402")
      (libsource (lib "eagle-import") (part "C-USC0402"))
    )
    (comp (ref "D3")
      (value "DFLU1200")
      (footprint "eagle-import:DFLU1200")
      (libsource (lib "eagle-import") (part "DFLU1200"))
    )
    (comp (ref "D4")
      (value "DFLU1200")
      (footprint "eagle-import:DFLU1200")
      (libsource (lib "eagle-import") (part "DFLU1200"))
    )
    (comp (ref "D5")
      (value "DFLU1200")
      (footprint "eagle-import:DFLU1200")
      (libsource (lib "eagle-import") (part "DFLU1200"))
    )
    (comp (ref "D6")
      (value "DFLU1200")
      (footprint "eagle-import:DFLU1200")
      (libsource (lib "eagle-import") (part "DFLU1200"))
    )
    (comp (ref "D7")
      (value "DFLU1200")
      (footprint "eagle-import:DFLU1200")
      (libsource (lib "eagle-import") (part "DFLU1200"))
    )
    (comp (ref "D8")
      (value "DFLU1200")
      (footprint "eagle-import:DFLU1200")
      (libsource (lib "eagle-import") (part "DFLU1200"))
    )
    (comp (ref "D9")
      (value "DFLU1200")
      (footprint "eagle-import:DFLU1200")
      (libsource (lib "eagle-import") (part "DFLU1200"))
    )
    (comp (ref "D10")
      (value "DFLU1200")
      (footprint "eagle-import:DFLU1200")
      (libsource (lib "eagle-import") (part "DFLU1200"))
    )
    (comp (ref "Q5")
      (value "2N7002K-7")
      (footprint "eagle-import:2N7002K-7")
      (libsource (lib "eagle-import") (part "2N7002K-7"))
    )
    (comp (ref "Q6")
      (value "BSS138K")
      (footprint "eagle-import:BSS138K")
      (libsource (lib "eagle-import") (part "BSS138K"))
    )
    (comp (ref "Q7")
      (value "2N7002K-7")
      (footprint "eagle-import:2N7002K-7")
      (libsource (lib "eagle-import") (part "2N7002K-7"))
    )
    (comp (ref "Q8")
      (value "BSS138K")
      (footprint "eagle-import:BSS138K")
      (libsource (lib "eagle-import") (part "BSS138K"))
    )
    (comp (ref "Q9")
      (value "2N7002K-7")
      (footprint "eagle-import:2N7002K-7")
      (libsource (lib "eagle-import") (part "2N7002K-7"))
    )
    (comp (ref "Q10")
      (value "BSS138K")
      (footprint "eagle-import:BSS138K")
      (libsource (lib "eagle-import") (part "BSS138K"))
    )
    (comp (ref "Q11")
      (value "2N7002K-7")
      (footprint "eagle-import:2N7002K-7")
      (libsource (lib "eagle-import") (part "2N7002K-7"))
    )
    (comp (ref "Q12")
      (value "BSS138K")
      (footprint "eagle-import:BSS138K")
      (libsource (lib "eagle-import") (part "BSS138K"))
    )
    (comp (ref "Q13")
      (value "2N7002K-7")
      (footprint "eagle-import:2N7002K-7")
      (libsource (lib "eagle-import") (part "2N7002K-7"))
    )
    (comp (ref "Q14")
      (value "BSS138K")
      (footprint "eagle-import:BSS138K")
      (libsource (lib "eagle-import") (part "BSS138K"))
    )
    (comp (ref "Q15")
      (value "2N7002K-7")
      (footprint "eagle-import:2N7002K-7")
      (libsource (lib "eagle-import") (part "2N7002K-7"))
    )
    (comp (ref "Q16")
      (value "BSS138K")
      (footprint "eagle-import:BSS138K")
      (libsource (lib "eagle-import") (part "BSS138K"))
    )
    (comp (ref "Q17")
      (value "2N7002K-7")
      (footprint "eagle-import:2N7002K-7")
      (libsource (lib "eagle-import") (part "2N7002K-7"))
    )
    (comp (ref "Q18")
      (value "BSS138K")
      (footprint "eagle-import:BSS138K")
      (libsource (lib "eagle-import") (part "BSS138K"))
    )
    (comp (ref "Q19")
      (value "2N7002K-7")
      (footprint "eagle-import:2N7002K-7")
      (libsource (lib "eagle-import") (part "2N7002K-7"))
    )
    (comp (ref "Q20")
      (value "BSS138K")
      (footprint "eagle-import:BSS138K")
      (libsource (lib "eagle-import") (part "BSS138K"))
    )
    (comp (ref "R7")
      (value "1M")
      (footprint "eagle-import:R0402")
      (libsource (lib "eagle-import") (part "R-US_R0402"))
    )
    (comp (ref "R8")
      (value "100k")
      (footprint "eagle-import:R0402")
      (libsource (lib "eagle-import") (part "R-US_R0402"))
    )
    (comp (ref "R9")
      (value "100k")
      (footprint "eagle-import:R0402")
      (libsource (lib "eagle-import") (part "R-US_R0402"))
    )
    (comp (ref "R10")
      (value "1M")
      (footprint "eagle-import:R0402")
      (libsource (lib "eagle-import") (part "R-US_R0402"))
    )
    (comp (ref "R11")
      (value "100k")
      (footprint "eagle-import:R0402")
      (libsource (lib "eagle-import") (part "R-US_R0402"))
    )
    (comp (ref "R12")
      (value "100k")
      (footprint "eagle-import:R0402")
      (libsource (lib "eagle-import") (part "R-US_R0402"))
    )
    (comp (ref "R13")
      (value "1M")
      (footprint "eagle-import:R0402")
      (libsource (lib "eagle-import") (part "R-US_R0402"))
    )
    (comp (ref "R14")
      (value "100k")
      (footprint "eagle-import:R0402")
      (libsource (lib "eagle-import") (part "R-US_R0402"))
    )
    (comp (ref "R15")
      (value "100k")
      (footprint "eagle-import:R0402")
      (libsource (lib "eagle-import") (part "R-US_R0402"))
    )
    (comp (ref "R16")
      (value "1M")
      (footprint "eagle-import:R0402")
      (libsource (lib "eagle-import") (part "R-US_R0402"))
    )
    (comp (ref "R17")
      (value "100k")
      (footprint "eagle-import:R0402")
      (libsource (lib "eagle-import") (part "R-US_R0402"))
    )
    (comp (ref "R18")
      (value "100k")
      (footprint "eagle-import:R0402")
      (libsource (lib "eagle-import") (part "R-US_R0402"))
    )
    (comp (ref "R19")
      (value "1M")
      (footprint "eagle-import:R0402")
      (libsource (lib "eagle-import") (part "R-US_R0402"))
    )
    (comp (ref "R20")
      (value "100k")
      (footprint "eagle-import:R0402")
      (libsource (lib "eagle-import") (part "R-US_R0402"))
    )
    (comp (ref "R21")
      (value "100k")
      (footprint "eagle-import:R0402")
      (libsource (lib "eagle-import") (part "R-US_R0402"))
    )
    (comp (ref "R22")
      (value "1M")
      (footprint "eagle-import:R0402")
      (libsource (lib "eagle-import") (part "R-US_R0402"))
    )
    (comp (ref "R23")
      (value "100k")
      (footprint "eagle-import:R0402")
      (libsource (lib "eagle-import") (part "R-US_R0402"))
    )
    (comp (ref "R24")
      (value "100k")
      (footprint "eagle-import:R0402")
      (libsource (lib "eagle-import") (part "R-US_R0402"))
    )
    (comp (ref "R25")
      (value "1M")
      (footprint "eagle-import:R0402")
      (libsource (lib "eagle-import") (part "R-US_R0402"))
    )
    (comp (ref "R26")
      (value "100k")
      (footprint "eagle-import:R0402")
      (libsource (lib "eagle-import") (part "R-US_R0402"))
    )
    (comp (ref "R27")
      (value "100k")
      (footprint "eagle-import:R0402")
      (libsource (lib "eagle-import") (part "R-US_R0402"))
    )
    (comp (ref "R28")
      (value "1M")
      (footprint "eagle-import:R0402")
      (libsource (lib "eagle-import") (part "R-US_R0402"))
    )
    (comp (ref "R29")
      (value "100k")
      (footprint "eagle-import:R0402")
      (libsource (lib "eagle-import") (part "R-US_R0402"))
    )
    (comp (ref "R30")
      (value "100k")
      (footprint "eagle-import:R0402")
      (libsource (lib "eagle-import") (part "R-US_R0402"))
    )
    (comp (ref "U2")
      (value "CDBHD140L-G")
      (footprint "eagle-import:CDBHDXX0L-G")
      (libsource (lib "eagle-import") (part "CDBHD140L-G"))
    )
    (comp (ref "U3")
      (value "CDBHD140L-G")
      (footprint "eagle-import:CDBHDXX0L-G")
      (libsource (lib "eagle-import") (part "CDBHD140L-G"))
    )
    (comp (ref "U4")
      (value "CDBHD140L-G")
      (footprint "eagle-import:CDBHDXX0L-G")
      (libsource (lib "eagle-import") (part "CDBHD140L-G"))
    )
    (comp (ref "U5")
      (value "CDBHD140L-G")
      (footprint "eagle-import:CDBHDXX0L-G")
      (libsource (lib "eagle-import") (part "CDBHD140L-G"))
    )
    (comp (ref "AF14")
      (value "BUTTON-MOUNT")
      (footprint "eagle-import:BUTTON-MOUNT")
      (libsource (lib "eagle-import") (part "BUTTON-MOUNT"))
    )
    (comp (ref "AF16")
      (value "BUTTON-MOUNT")
      (footprint "eagle-import:BUTTON-MOUNT")
      (libsource (lib "eagle-import") (part "BUTTON-MOUNT"))
    )
    (comp (ref "AF18")
      (value "BUTTON-MOUNT")
      (footprint "eagle-import:BUTTON-MOUNT")
      (libsource (lib "eagle-import") (part "BUTTON-MOUNT"))
    )
    (comp (ref "AF20")
      (value "BUTTON-MOUNT")
      (footprint "eagle-import:BUTTON-MOUNT")
      (libsource (lib "eagle-import") (part "BUTTON-MOUNT"))
    )
    (comp (ref "C27")
      (value "10n")
      (footprint "eagle-import:C0402")
      (libsource (lib "eagle-import") (part "C-USC0402"))
    )
    (comp (ref "C28")
      (value "10n")
      (footprint "eagle-import:C0402")
      (libsource (lib "eagle-import") (part "C-USC0402"))
    )
    (comp (ref "C31")
      (value "10n")
      (footprint "eagle-import:C0402")
      (libsource (lib "eagle-import") (part "C-USC0402"))
    )
    (comp (ref "C32")
      (value "10n")
      (footprint "eagle-import:C0402")
      (libsource (lib "eagle-import") (part "C-USC0402"))
    )
    (comp (ref "C35")
      (value "10n")
      (footprint "eagle-import:C0402")
      (libsource (lib "eagle-import") (part "C-USC0402"))
    )
    (comp (ref "C36")
      (value "10n")
      (footprint "eagle-import:C0402")
      (libsource (lib "eagle-import") (part "C-USC0402"))
    )
    (comp (ref "C39")
      (value "10n")
      (footprint "eagle-import:C0402")
      (libsource (lib "eagle-import") (part "C-USC0402"))
    )
    (comp (ref "C40")
      (value "10n")
      (footprint "eagle-import:C0402")
      (libsource (lib "eagle-import") (part "C-USC0402"))
    )
    (comp (ref "D27")
      (value "DFLU1200")
      (footprint "eagle-import:DFLU1200")
      (libsource (lib "eagle-import") (part "DFLU1200"))
    )
    (comp (ref "D28")
      (value "DFLU1200")
      (footprint "eagle-import:DFLU1200")
      (libsource (lib "eagle-import") (part "DFLU1200"))
    )
    (comp (ref "D31")
      (value "DFLU1200")
      (footprint "eagle-import:DFLU1200")
      (libsource (lib "eagle-import") (part "DFLU1200"))
    )
    (comp (ref "D32")
      (value "DFLU1200")
      (footprint "eagle-import:DFLU1200")
      (libsource (lib "eagle-import") (part "DFLU1200"))
    )
    (comp (ref "D35")
      (value "DFLU1200")
      (footprint "eagle-import:DFLU1200")
      (libsource (lib "eagle-import") (part "DFLU1200"))
    )
    (comp (ref "D36")
      (value "DFLU1200")
      (footprint "eagle-import:DFLU1200")
      (libsource (lib "eagle-import") (part "DFLU1200"))
    )
    (comp (ref "D39")
      (value "DFLU1200")
      (footprint "eagle-import:DFLU1200")
      (libsource (lib "eagle-import") (part "DFLU1200"))
    )
    (comp (ref "D40")
      (value "DFLU1200")
      (footprint "eagle-import:DFLU1200")
      (libsource (lib "eagle-import") (part "DFLU1200"))
    )
    (comp (ref "Q53")
      (value "2N7002K-7")
      (footprint "eagle-import:2N7002K-7")
      (libsource (lib "eagle-import") (part "2N7002K-7"))
    )
    (comp (ref "Q54")
      (value "BSS138K")
      (footprint "eagle-import:BSS138K")
      (libsource (lib "eagle-import") (part "BSS138K"))
    )
    (comp (ref "Q55")
      (value "2N7002K-7")
      (footprint "eagle-import:2N7002K-7")
      (libsource (lib "eagle-import") (part "2N7002K-7"))
    )
    (comp (ref "Q56")
      (value "BSS138K")
      (footprint "eagle-import:BSS138K")
      (libsource (lib "eagle-import") (part "BSS138K"))
    )
    (comp (ref "Q61")
      (value "2N7002K-7")
      (footprint "eagle-import:2N7002K-7")
      (libsource (lib "eagle-import") (part "2N7002K-7"))
    )
    (comp (ref "Q62")
      (value "BSS138K")
      (footprint "eagle-import:BSS138K")
      (libsource (lib "eagle-import") (part "BSS138K"))
    )
    (comp (ref "Q63")
      (value "2N7002K-7")
      (footprint "eagle-import:2N7002K-7")
      (libsource (lib "eagle-import") (part "2N7002K-7"))
    )
    (comp (ref "Q64")
      (value "BSS138K")
      (footprint "eagle-import:BSS138K")
      (libsource (lib "eagle-import") (part "BSS138K"))
    )
    (comp (ref "Q69")
      (value "2N7002K-7")
      (footprint "eagle-import:2N7002K-7")
      (libsource (lib "eagle-import") (part "2N7002K-7"))
    )
    (comp (ref "Q70")
      (value "BSS138K")
      (footprint "eagle-import:BSS138K")
      (libsource (lib "eagle-import") (part "BSS138K"))
    )
    (comp (ref "Q71")
      (value "2N7002K-7")
      (footprint "eagle-import:2N7002K-7")
      (libsource (lib "eagle-import") (part "2N7002K-7"))
    )
    (comp (ref "Q72")
      (value "BSS138K")
      (footprint "eagle-import:BSS138K")
      (libsource (lib "eagle-import") (part "BSS138K"))
    )
    (comp (ref "Q77")
      (value "2N7002K-7")
      (footprint "eagle-import:2N7002K-7")
      (libsource (lib "eagle-import") (part "2N7002K-7"))
    )
    (comp (ref "Q78")
      (value "BSS138K")
      (footprint "eagle-import:BSS138K")
      (libsource (lib "eagle-import") (part "BSS138K"))
    )
    (comp (ref "Q79")
      (value "2N7002K-7")
      (footprint "eagle-import:2N7002K-7")
      (libsource (lib "eagle-import") (part "2N7002K-7"))
    )
    (comp (ref "Q80")
      (value "BSS138K")
      (footprint "eagle-import:BSS138K")
      (libsource (lib "eagle-import") (part "BSS138K"))
    )
    (comp (ref "R79")
      (value "1M")
      (footprint "eagle-import:R0402")
      (libsource (lib "eagle-import") (part "R-US_R0402"))
    )
    (comp (ref "R80")
      (value "100k")
      (footprint "eagle-import:R0402")
      (libsource (lib "eagle-import") (part "R-US_R0402"))
    )
    (comp (ref "R81")
      (value "100k")
      (footprint "eagle-import:R0402")
      (libsource (lib "eagle-import") (part "R-US_R0402"))
    )
    (comp (ref "R82")
      (value "1M")
      (footprint "eagle-import:R0402")
      (libsource (lib "eagle-import") (part "R-US_R0402"))
    )
    (comp (ref "R83")
      (value "100k")
      (footprint "eagle-import:R0402")
      (libsource (lib "eagle-import") (part "R-US_R0402"))
    )
    (comp (ref "R84")
      (value "100k")
      (footprint "eagle-import:R0402")
      (libsource (lib "eagle-import") (part "R-US_R0402"))
    )
    (comp (ref "R91")
      (value "1M")
      (footprint "eagle-import:R0402")
      (libsource (lib "eagle-import") (part "R-US_R0402"))
    )
    (comp (ref "R92")
      (value "100k")
      (footprint "eagle-import:R0402")
      (libsource (lib "eagle-import") (part "R-US_R0402"))
    )
    (comp (ref "R93")
      (value "100k")
      (footprint "eagle-import:R0402")
      (libsource (lib "eagle-import") (part "R-US_R0402"))
    )
    (comp (ref "R94")
      (value "1M")
      (footprint "eagle-import:R0402")
      (libsource (lib "eagle-import") (part "R-US_R0402"))
    )
    (comp (ref "R95")
      (value "100k")
      (footprint "eagle-import:R0402")
      (libsource (lib "eagle-import") (part "R-US_R0402"))
    )
    (comp (ref "R96")
      (value "100k")
      (footprint "eagle-import:R0402")
      (libsource (lib "eagle-import") (part "R-US_R0402"))
    )
    (comp (ref "R103")
      (value "1M")
      (footprint "eagle-import:R0402")
      (libsource (lib "eagle-import") (part "R-US_R0402"))
    )
    (comp (ref "R104")
      (value "100k")
      (footprint "eagle-import:R0402")
      (libsource (lib "eagle-import") (part "R-US_R0402"))
    )
    (comp (ref "R105")
      (value "100k")
      (footprint "eagle-import:R0402")
      (libsource (lib "eagle-import") (part "R-US_R0402"))
    )
    (comp (ref "R106")
      (value "1M")
      (footprint "eagle-import:R0402")
      (libsource (lib "eagle-import") (part "R-US_R0402"))
    )
    (comp (ref "R107")
      (value "100k")
      (footprint "eagle-import:R0402")
      (libsource (lib "eagle-import") (part "R-US_R0402"))
    )
    (comp (ref "R108")
      (value "100k")
      (footprint "eagle-import:R0402")
      (libsource (lib "eagle-import") (part "R-US_R0402"))
    )
    (comp (ref "R115")
      (value "1M")
      (footprint "eagle-import:R0402")
      (libsource (lib "eagle-import") (part "R-US_R0402"))
    )
    (comp (ref "R116")
      (value "100k")
      (footprint "eagle-import:R0402")
      (libsource (lib "eagle-import") (part "R-US_R0402"))
    )
    (comp (ref "R117")
      (value "100k")
      (footprint "eagle-import:R0402")
      (libsource (lib "eagle-import") (part "R-US_R0402"))
    )
    (comp (ref "R118")
      (value "1M")
      (footprint "eagle-import:R0402")
      (libsource (lib "eagle-import") (part "R-US_R0402"))
    )
    (comp (ref "R119")
      (value "100k")
      (footprint "eagle-import:R0402")
      (libsource (lib "eagle-import") (part "R-US_R0402"))
    )
    (comp (ref "R120")
      (value "100k")
      (footprint "eagle-import:R0402")
      (libsource (lib "eagle-import") (part "R-US_R0402"))
    )
    (comp (ref "U14")
      (value "CDBHD140L-G")
      (footprint "eagle-import:CDBHDXX0L-G")
      (libsource (lib "eagle-import") (part "CDBHD140L-G"))
    )
    (comp (ref "U16")
      (value "CDBHD140L-G")
      (footprint "eagle-import:CDBHDXX0L-G")
      (libsource (lib "eagle-import") (part "CDBHD140L-G"))
    )
    (comp (ref "U18")
      (value "CDBHD140L-G")
      (footprint "eagle-import:CDBHDXX0L-G")
      (libsource (lib "eagle-import") (part "CDBHD140L-G"))
    )
    (comp (ref "U20")
      (value "CDBHD140L-G")
      (footprint "eagle-import:CDBHDXX0L-G")
      (libsource (lib "eagle-import") (part "CDBHD140L-G"))
    )
  )
  (nets
    (net (code "1") (name "BTN0_DOWN_CAP") (class "Default")
      (node (ref "C4") (pin "1") (pinfunction "1_1") (pintype "passive"))
      (node (ref "D4") (pin "K") (pinfunction "K_K") (pintype "bidirectional"))
      (node (ref "Q7") (pin "G") (pinfunction "G_G") (pintype "bidirectional"))
      (node (ref "Q8") (pin "D") (pinfunction "D_D") (pintype "bidirectional"))
    )
    (net (code "2") (name "BTN0_DOWN_CLR") (class "Default")
      (node (ref "Q8") (pin "G") (pinfunction "G_G") (pintype "bidirectional"))
      (node (ref "R11") (pin "2") (pinfunction "2_2") (pintype "passive"))
    )
    (net (code "3") (name "BTN0_DOWN_SENSE") (class "Default")
      (node (ref "Q7") (pin "D") (pinfunction "D_D") (pintype "bidirectional"))
      (node (ref "R12") (pin "1") (pinfunction "1_1") (pintype "passive"))
    )
    (net (code "4") (name "BTN0_PIN1") (class "Default")
      (node (ref "AF2") (pin "P$1") (pinfunction "P$1_P$1") (pintype "bidirectional"))
      (node (ref "D3") (pin "A") (pinfunction "A_A") (pintype "bidirectional"))
      (node (ref "R7") (pin "2") (pinfunction "2_2") (pintype "passive"))
      (node (ref "U2") (pin "P$4") (pinfunction "P$4_P$4") (pintype "bidirectional"))
    )
    (net (code "5") (name "BTN0_PIN3") (class "Default")
      (node (ref "AF2") (pin "P$2") (pinfunction "P$2_P$2") (pintype "bidirectional"))
      (node (ref "D4") (pin "A") (pinfunction "A_A") (pintype "bidirectional"))
      (node (ref "R10") (pin "2") (pinfunction "2_2") (pintype "passive"))
      (node (ref "U2") (pin "P$3") (pinfunction "P$3_P$3") (pintype "bidirectional"))
    )
    (net (code "6") (name "BTN0_UP_CAP") (class "Default")
      (node (ref "C3") (pin "1") (pinfunction "1_1") (pintype "passive"))
      (node (ref "D3") (pin "K") (pinfunction "K_K") (pintype "bidirectional"))
      (node (ref "Q5") (pin "G") (pinfunction "G_G") (pintype "bidirectional"))
      (node (ref "Q6") (pin "D") (pinfunction "D_D") (pintype "bidirectional"))
    )
    (net (code "7") (name "BTN0_UP_CLR") (class "Default")
      (node (ref "Q6") (pin "G") (pinfunction "G_G") (pintype "bidirectional"))
      (node (ref "R9") (pin "2") (pinfunction "2_2") (pintype "passive"))
    )
    (net (code "8") (name "BTN0_UP_SENSE") (class "Default")
      (node (ref "Q5") (pin "D") (pinfunction "D_D") (pintype "bidirectional"))
      (node (ref "R8") (pin "1") (pinfunction "1_1") (pintype "passive"))
    )
    (net (code "9") (name "BTN1_DOWN_CAP") (class "Default")
      (node (ref "C6") (pin "1") (pinfunction "1_1") (pintype "passive"))
      (node (ref "D6") (pin "K") (pinfunction "K_K") (pintype "bidirectional"))
      (node (ref "Q11") (pin "G") (pinfunction "G_G") (pintype "bidirectional"))
      (node (ref "Q12") (pin "D") (pinfunction "D_D") (pintype "bidirectional"))
    )
    (net (code "10") (name "BTN1_DOWN_CLR") (class "Default")
      (node (ref "Q12") (pin "G") (pinfunction "G_G") (pintype "bidirectional"))
      (node (ref "R17") (pin "2") (pinfunction "2_2") (pintype "passive"))
    )
    (net (code "11") (name "BTN1_DOWN_SENSE") (class "Default")
      (node (ref "Q11") (pin "D") (pinfunction "D_D") (pintype "bidirectional"))
      (node (ref "R18") (pin "1") (pinfunction "1_1") (pintype "passive"))
    )
    (net (code "12") (name "BTN1_PIN1") (class "Default")
      (node (ref "AF3") (pin "P$1") (pinfunction "P$1_P$1") (pintype "bidirectional"))
      (node (ref "D5") (pin "A") (pinfunction "A_A") (pintype "bidirectional"))
      (node (ref "R13") (pin "2") (pinfunction "2_2") (pintype "passive"))
      (node (ref "U3") (pin "P$4") (pinfunction "P$4_P$4") (pintype "bidirectional"))
    )
    (net (code "13") (name "BTN1_PIN3") (class "Default")
      (node (ref "AF3") (pin "P$2") (pinfunction "P$2_P$2") (pintype "bidirectional"))
      (node (ref "D6") (pin "A") (pinfunction "A_A") (pintype "bidirectional"))
      (node (ref "R16") (pin "2") (pinfunction "2_2") (pintype "passive"))
      (node (ref "U3") (pin "P$3") (pinfunction "P$3_P$3") (pintype "bidirectional"))
    )
    (net (code "14") (name "BTN1_UP_CAP") (class "Default")
      (node (ref "C5") (pin "1") (pinfunction "1_1") (pintype "passive"))
      (node (ref "D5") (pin "K") (pinfunction "K_K") (pintype "bidirectional"))
      (node (ref "Q10") (pin "D") (pinfunction "D_D") (pintype "bidirectional"))
      (node (ref "Q9") (pin "G") (pinfunction "G_G") (pintype "bidirectional"))
    )
    (net (code "15") (name "BTN1_UP_CLR") (class "Default")
      (node (ref "Q10") (pin "G") (pinfunction "G_G") (pintype "bidirectional"))
      (node (ref "R15") (pin "2") (pinfunction "2_2") (pintype "passive"))
    )
    (net (code "16") (name "BTN1_UP_SENSE") (class "Default")
      (node (ref "Q9") (pin "D") (pinfunction "D_D") (pintype "bidirectional"))
      (node (ref "R14") (pin "1") (pinfunction "1_1") (pintype "passive"))
    )
    (net (code "17") (name "BTN2_DOWN_CAP") (class "Default")
      (node (ref "C8") (pin "1") (pinfunction "1_1") (pintype "passive"))
      (node (ref "D8") (pin "K") (pinfunction "K_K") (pintype "bidirectional"))
      (node (ref "Q15") (pin "G") (pinfunction "G_G") (pintype "bidirectional"))
      (node (ref "Q16") (pin "D") (pinfunction "D_D") (pintype "bidirectional"))
    )
    (net (code "18") (name "BTN2_DOWN_CLR") (class "Default")
      (node (ref "Q16") (pin "G") (pinfunction "G_G") (pintype "bidirectional"))
      (node (ref "R23") (pin "2") (pinfunction "2_2") (pintype "passive"))
    )
    (net (code "19") (name "BTN2_DOWN_SENSE") (class "Default")
      (node (ref "Q15") (pin "D") (pinfunction "D_D") (pintype "bidirectional"))
      (node (ref "R24") (pin "1") (pinfunction "1_1") (pintype "passive"))
    )
    (net (code "20") (name "BTN2_PIN1") (class "Default")
      (node (ref "AF4") (pin "P$1") (pinfunction "P$1_P$1") (pintype "bidirectional"))
      (node (ref "D7") (pin "A") (pinfunction "A_A") (pintype "bidirectional"))
      (node (ref "R19") (pin "2") (pinfunction "2_2") (pintype "passive"))
      (node (ref "U4") (pin "P$4") (pinfunction "P$4_P$4") (pintype "bidirectional"))
    )
    (net (code "21") (name "BTN2_PIN3") (class "Default")
      (node (ref "AF4") (pin "P$2") (pinfunction "P$2_P$2") (pintype "bidirectional"))
      (node (ref "D8") (pin "A") (pinfunction "A_A") (pintype "bidirectional"))
      (node (ref "R22") (pin "2") (pinfunction "2_2") (pintype "passive"))
      (node (ref "U4") (pin "P$3") (pinfunction "P$3_P$3") (pintype "bidirectional"))
    )
    (net (code "22") (name "BTN2_UP_CAP") (class "Default")
      (node (ref "C7") (pin "1") (pinfunction "1_1") (pintype "passive"))
      (node (ref "D7") (pin "K") (pinfunction "K_K") (pintype "bidirectional"))
      (node (ref "Q13") (pin "G") (pinfunction "G_G") (pintype "bidirectional"))
      (node (ref "Q14") (pin "D") (pinfunction "D_D") (pintype "bidirectional"))
    )
    (net (code "23") (name "BTN2_UP_CLR") (class "Default")
      (node (ref "Q14") (pin "G") (pinfunction "G_G") (pintype "bidirectional"))
      (node (ref "R21") (pin "2") (pinfunction "2_2") (pintype "passive"))
    )
    (net (code "24") (name "BTN2_UP_SENSE") (class "Default")
      (node (ref "Q13") (pin "D") (pinfunction "D_D") (pintype "bidirectional"))
      (node (ref "R20") (pin "1") (pinfunction "1_1") (pintype "passive"))
    )
    (net (code "25") (name "BTN3_DOWN_CAP") (class "Default")
      (node (ref "C10") (pin "1") (pinfunction "1_1") (pintype "passive"))
      (node (ref "D10") (pin "K") (pinfunction "K_K") (pintype "bidirectional"))
      (node (ref "Q19") (pin "G") (pinfunction "G_G") (pintype "bidirectional"))
      (node (ref "Q20") (pin "D") (pinfunction "D_D") (pintype "bidirectional"))
    )
    (net (code "26") (name "BTN3_DOWN_CLR") (class "Default")
      (node (ref "Q20") (pin "G") (pinfunction "G_G") (pintype "bidirectional"))
      (node (ref "R29") (pin "2") (pinfunction "2_2") (pintype "passive"))
    )
    (net (code "27") (name "BTN3_DOWN_SENSE") (class "Default")
      (node (ref "Q19") (pin "D") (pinfunction "D_D") (pintype "bidirectional"))
      (node (ref "R30") (pin "1") (pinfunction "1_1") (pintype "passive"))
    )
    (net (code "28") (name "BTN3_PIN1") (class "Default")
      (node (ref "AF5") (pin "P$1") (pinfunction "P$1_P$1") (pintype "bidirectional"))
      (node (ref "D9") (pin "A") (pinfunction "A_A") (pintype "bidirectional"))
      (node (ref "R25") (pin "2") (pinfunction "2_2") (pintype "passive"))
      (node (ref "U5") (pin "P$4") (pinfunction "P$4_P$4") (pintype "bidirectional"))
    )
    (net (code "29") (name "BTN3_PIN3") (class "Default")
      (node (ref "AF5") (pin "P$2") (pinfunction "P$2_P$2") (pintype "bidirectional"))
      (node (ref "D10") (pin "A") (pinfunction "A_A") (pintype "bidirectional"))
      (node (ref "R28") (pin "2") (pinfunction "2_2") (pintype "passive"))
      (node (ref "U5") (pin "P$3") (pinfunction "P$3_P$3") (pintype "bidirectional"))
    )
    (net (code "30") (name "BTN3_UP_CAP") (class "Default")
      (node (ref "C9") (pin "1") (pinfunction "1_1") (pintype "passive"))
      (node (ref "D9") (pin "K") (pinfunction "K_K") (pintype "bidirectional"))
      (node (ref "Q17") (pin "G") (pinfunction "G_G") (pintype "bidirectional"))
      (node (ref "Q18") (pin "D") (pinfunction "D_D") (pintype "bidirectional"))
    )
    (net (code "31") (name "BTN3_UP_CLR") (class "Default")
      (node (ref "Q18") (pin "G") (pinfunction "G_G") (pintype "bidirectional"))
      (node (ref "R27") (pin "2") (pinfunction "2_2") (pintype "passive"))
    )
    (net (code "32") (name "BTN3_UP_SENSE") (class "Default")
      (node (ref "Q17") (pin "D") (pinfunction "D_D") (pintype "bidirectional"))
      (node (ref "R26") (pin "1") (pinfunction "1_1") (pintype "passive"))
    )
    (net (code "33") (name "BTN4_DOWN_CAP") (class "Default")
      (node (ref "C12") (pin "1") (pinfunction "1_1") (pintype "passive"))
      (node (ref "D12") (pin "K") (pinfunction "K_K") (pintype "bidirectional"))
      (node (ref "Q23") (pin "G") (pinfunction "G_G") (pintype "bidirectional"))
      (node (ref "Q24") (pin "D") (pinfunction "D_D") (pintype "bidirectional"))
    )
    (net (code "34") (name "BTN4_DOWN_CLR") (class "Default")
      (node (ref "Q24") (pin "G") (pinfunction "G_G") (pintype "bidirectional"))
      (node (ref "R35") (pin "2") (pinfunction "2_2") (pintype "passive"))
    )
    (net (code "35") (name "BTN4_DOWN_SENSE") (class "Default")
      (node (ref "Q23") (pin "D") (pinfunction "D_D") (pintype "bidirectional"))
      (node (ref "R36") (pin "1") (pinfunction "1_1") (pintype "passive"))
    )
    (net (code "36") (name "BTN4_PIN1") (class "Default")
      (node (ref "AF6") (pin "P$1") (pinfunction "P$1_P$1") (pintype "bidirectional"))
      (node (ref "D11") (pin "A") (pinfunction "A_A") (pintype "bidirectional"))
      (node (ref "R31") (pin "2") (pinfunction "2_2") (pintype "passive"))
      (node (ref "U6") (pin "P$4") (pinfunction "P$4_P$4") (pintype "bidirectional"))
    )
    (net (code "37") (name "BTN4_PIN3") (class "Default")
      (node (ref "AF6") (pin "P$2") (pinfunction "P$2_P$2") (pintype "bidirectional"))
      (node (ref "D12") (pin "A") (pinfunction "A_A") (pintype "bidirectional"))
      (node (ref "R34") (pin "2") (pinfunction "2_2") (pintype "passive"))
      (node (ref "U6") (pin "P$3") (pinfunction "P$3_P$3") (pintype "bidirectional"))
    )
    (net (code "38") (name "BTN4_UP_CAP") (class "Default")
      (node (ref "C11") (pin "1") (pinfunction "1_1") (pintype "passive"))
      (node (ref "D11") (pin "K") (pinfunction "K_K") (pintype "bidirectional"))
      (node (ref "Q21") (pin "G") (pinfunction "G_G") (pintype "bidirectional"))
      (node (ref "Q22") (pin "D") (pinfunction "D_D") (pintype "bidirectional"))
    )
    (net (code "39") (name "BTN4_UP_CLR") (class "Default")
      (node (ref "Q22") (pin "G") (pinfunction "G_G") (pintype "bidirectional"))
      (node (ref "R33") (pin "2") (pinfunction "2_2") (pintype "passive"))
    )
    (net (code "40") (name "BTN4_UP_SENSE") (class "Default")
      (node (ref "Q21") (pin "D") (pinfunction "D_D") (pintype "bidirectional"))
      (node (ref "R32") (pin "1") (pinfunction "1_1") (pintype "passive"))
    )
    (net (code "41") (name "BTN5_DOWN_CAP") (class "Default")
      (node (ref "C16") (pin "1") (pinfunction "1_1") (pintype "passive"))
      (node (ref "D16") (pin "K") (pinfunction "K_K") (pintype "bidirectional"))
      (node (ref "Q31") (pin "G") (pinfunction "G_G") (pintype "bidirectional"))
      (node (ref "Q32") (pin "D") (pinfunction "D_D") (pintype "bidirectional"))
    )
    (net (code "42") (name "BTN5_DOWN_CLR") (class "Default")
      (node (ref "Q32") (pin "G") (pinfunction "G_G") (pintype "bidirectional"))
      (node (ref "R47") (pin "2") (pinfunction "2_2") (pintype "passive"))
    )
    (net (code "43") (name "BTN5_DOWN_SENSE") (class "Default")
      (node (ref "Q31") (pin "D") (pinfunction "D_D") (pintype "bidirectional"))
      (node (ref "R48") (pin "1") (pinfunction "1_1") (pintype "passive"))
    )
    (net (code "44") (name "BTN5_PIN1") (class "Default")
      (node (ref "AF8") (pin "P$1") (pinfunction "P$1_P$1") (pintype "bidirectional"))
      (node (ref "D15") (pin "A") (pinfunction "A_A") (pintype "bidirectional"))
      (node (ref "R43") (pin "2") (pinfunction "2_2") (pintype "passive"))
      (node (ref "U8") (pin "P$4") (pinfunction "P$4_P$4") (pintype "bidirectional"))
    )
    (net (code "45") (name "BTN5_PIN3") (class "Default")
      (node (ref "AF8") (pin "P$2") (pinfunction "P$2_P$2") (pintype "bidirectional"))
      (node (ref "D16") (pin "A") (pinfunction "A_A") (pintype "bidirectional"))
      (node (ref "R46") (pin "2") (pinfunction "2_2") (pintype "passive"))
      (node (ref "U8") (pin "P$3") (pinfunction "P$3_P$3") (pintype "bidirectional"))
    )
    (net (code "46") (name "BTN5_UP_CAP") (class "Default")
      (node (ref "C15") (pin "1") (pinfunction "1_1") (pintype "passive"))
      (node (ref "D15") (pin "K") (pinfunction "K_K") (pintype "bidirectional"))
      (node (ref "Q29") (pin "G") (pinfunction "G_G") (pintype "bidirectional"))
      (node (ref "Q30") (pin "D") (pinfunction "D_D") (pintype "bidirectional"))
    )
    (net (code "47") (name "BTN5_UP_CLR") (class "Default")
      (node (ref "Q30") (pin "G") (pinfunction "G_G") (pintype "bidirectional"))
      (node (ref "R45") (pin "2") (pinfunction "2_2") (pintype "passive"))
    )
    (net (code "48") (name "BTN5_UP_SENSE") (class "Default")
      (node (ref "Q29") (pin "D") (pinfunction "D_D") (pintype "bidirectional"))
      (node (ref "R44") (pin "1") (pinfunction "1_1") (pintype "passive"))
    )
    (net (code "49") (name "BTN6_DOWN_CAP") (class "Default")
      (node (ref "C20") (pin "1") (pinfunction "1_1") (pintype "passive"))
      (node (ref "D20") (pin "K") (pinfunction "K_K") (pintype "bidirectional"))
      (node (ref "Q39") (pin "G") (pinfunction "G_G") (pintype "bidirectional"))
      (node (ref "Q40") (pin "D") (pinfunction "D_D") (pintype "bidirectional"))
    )
    (net (code "50") (name "BTN6_DOWN_CLR") (class "Default")
      (node (ref "Q40") (pin "G") (pinfunction "G_G") (pintype "bidirectional"))
      (node (ref "R59") (pin "2") (pinfunction "2_2") (pintype "passive"))
    )
    (net (code "51") (name "BTN6_DOWN_SENSE") (class "Default")
      (node (ref "Q39") (pin "D") (pinfunction "D_D") (pintype "bidirectional"))
      (node (ref "R60") (pin "1") (pinfunction "1_1") (pintype "passive"))
    )
    (net (code "52") (name "BTN6_PIN1") (class "Default")
      (node (ref "AF10") (pin "P$1") (pinfunction "P$1_P$1") (pintype "bidirectional"))
      (node (ref "D19") (pin "A") (pinfunction "A_A") (pintype "bidirectional"))
      (node (ref "R55") (pin "2") (pinfunction "2_2") (pintype "passive"))
      (node (ref "U10") (pin "P$4") (pinfunction "P$4_P$4") (pintype "bidirectional"))
    )
    (net (code "53") (name "BTN6_PIN3") (class "Default")
      (node (ref "AF10") (pin "P$2") (pinfunction "P$2_P$2") (pintype "bidirectional"))
      (node (ref "D20") (pin "A") (pinfunction "A_A") (pintype "bidirectional"))
      (node (ref "R58") (pin "2") (pinfunction "2_2") (pintype "passive"))
      (node (ref "U10") (pin "P$3") (pinfunction "P$3_P$3") (pintype "bidirectional"))
    )
    (net (code "54") (name "BTN6_UP_CAP") (class "Default")
      (node (ref "C19") (pin "1") (pinfunction "1_1") (pintype "passive"))
      (node (ref "D19") (pin "K") (pinfunction "K_K") (pintype "bidirectional"))
      (node (ref "Q37") (pin "G") (pinfunction "G_G") (pintype "bidirectional"))
      (node (ref "Q38") (pin "D") (pinfunction "D_D") (pintype "bidirectional"))
    )
    (net (code "55") (name "BTN6_UP_CLR") (class "Default")
      (node (ref "Q38") (pin "G") (pinfunction "G_G") (pintype "bidirectional"))
      (node (ref "R57") (pin "2") (pinfunction "2_2") (pintype "passive"))
    )
    (net (code "56") (name "BTN6_UP_SENSE") (class "Default")
      (node (ref "Q37") (pin "D") (pinfunction "D_D") (pintype "bidirectional"))
      (node (ref "R56") (pin "1") (pinfunction "1_1") (pintype "passive"))
    )
    (net (code "57") (name "BTN7_DOWN_CAP") (class "Default")
      (node (ref "C24") (pin "1") (pinfunction "1_1") (pintype "passive"))
      (node (ref "D24") (pin "K") (pinfunction "K_K") (pintype "bidirectional"))
      (node (ref "Q47") (pin "G") (pinfunction "G_G") (pintype "bidirectional"))
      (node (ref "Q48") (pin "D") (pinfunction "D_D") (pintype "bidirectional"))
    )
    (net (code "58") (name "BTN7_DOWN_CLR") (class "Default")
      (node (ref "Q48") (pin "G") (pinfunction "G_G") (pintype "bidirectional"))
      (node (ref "R71") (pin "2") (pinfunction "2_2") (pintype "passive"))
    )
    (net (code "59") (name "BTN7_DOWN_SENSE") (class "Default")
      (node (ref "Q47") (pin "D") (pinfunction "D_D") (pintype "bidirectional"))
      (node (ref "R72") (pin "1") (pinfunction "1_1") (pintype "passive"))
    )
    (net (code "60") (name "BTN7_PIN1") (class "Default")
      (node (ref "AF12") (pin "P$1") (pinfunction "P$1_P$1") (pintype "bidirectional"))
      (node (ref "D23") (pin "A") (pinfunction "A_A") (pintype "bidirectional"))
      (node (ref "R67") (pin "2") (pinfunction "2_2") (pintype "passive"))
      (node (ref "U12") (pin "P$4") (pinfunction "P$4_P$4") (pintype "bidirectional"))
    )
    (net (code "61") (name "BTN7_PIN3") (class "Default")
      (node (ref "AF12") (pin "P$2") (pinfunction "P$2_P$2") (pintype "bidirectional"))
      (node (ref "D24") (pin "A") (pinfunction "A_A") (pintype "bidirectional"))
      (node (ref "R70") (pin "2") (pinfunction "2_2") (pintype "passive"))
      (node (ref "U12") (pin "P$3") (pinfunction "P$3_P$3") (pintype "bidirectional"))
    )
    (net (code "62") (name "BTN7_UP_CAP") (class "Default")
      (node (ref "C23") (pin "1") (pinfunction "1_1") (pintype "passive"))
      (node (ref "D23") (pin "K") (pinfunction "K_K") (pintype "bidirectional"))
      (node (ref "Q45") (pin "G") (pinfunction "G_G") (pintype "bidirectional"))
      (node (ref "Q46") (pin "D") (pinfunction "D_D") (pintype "bidirectional"))
    )
    (net (code "63") (name "BTN7_UP_CLR") (class "Default")
      (node (ref "Q46") (pin "G") (pinfunction "G_G") (pintype "bidirectional"))
      (node (ref "R69") (pin "2") (pinfunction "2_2") (pintype "passive"))
    )
    (net (code "64") (name "BTN7_UP_SENSE") (class "Default")
      (node (ref "Q45") (pin "D") (pinfunction "D_D") (pintype "bidirectional"))
      (node (ref "R68") (pin "1") (pinfunction "1_1") (pintype "passive"))
    )
    (net (code "65") (name "BTN8_DOWN_CAP") (class "Default")
      (node (ref "C28") (pin "1") (pinfunction "1_1") (pintype "passive"))
      (node (ref "D28") (pin "K") (pinfunction "K_K") (pintype "bidirectional"))
      (node (ref "Q55") (pin "G") (pinfunction "G_G") (pintype "bidirectional"))
      (node (ref "Q56") (pin "D") (pinfunction "D_D") (pintype "bidirectional"))
    )
    (net (code "66") (name "BTN8_DOWN_CLR") (class "Default")
      (node (ref "Q56") (pin "G") (pinfunction "G_G") (pintype "bidirectional"))
      (node (ref "R83") (pin "2") (pinfunction "2_2") (pintype "passive"))
    )
    (net (code "67") (name "BTN8_DOWN_SENSE") (class "Default")
      (node (ref "Q55") (pin "D") (pinfunction "D_D") (pintype "bidirectional"))
      (node (ref "R84") (pin "1") (pinfunction "1_1") (pintype "passive"))
    )
    (net (code "68") (name "BTN8_PIN1") (class "Default")
      (node (ref "AF14") (pin "P$1") (pinfunction "P$1_P$1") (pintype "bidirectional"))
      (node (ref "D27") (pin "A") (pinfunction "A_A") (pintype "bidirectional"))
      (node (ref "R79") (pin "2") (pinfunction "2_2") (pintype "passive"))
      (node (ref "U14") (pin "P$4") (pinfunction "P$4_P$4") (pintype "bidirectional"))
    )
    (net (code "69") (name "BTN8_PIN3") (class "Default")
      (node (ref "AF14") (pin "P$2") (pinfunction "P$2_P$2") (pintype "bidirectional"))
      (node (ref "D28") (pin "A") (pinfunction "A_A") (pintype "bidirectional"))
      (node (ref "R82") (pin "2") (pinfunction "2_2") (pintype "passive"))
      (node (ref "U14") (pin "P$3") (pinfunction "P$3_P$3") (pintype "bidirectional"))
    )
    (net (code "70") (name "BTN8_UP_CAP") (class "Default")
      (node (ref "C27") (pin "1") (pinfunction "1_1") (pintype "passive"))
      (node (ref "D27") (pin "K") (pinfunction "K_K") (pintype "bidirectional"))
      (node (ref "Q53") (pin "G") (pinfunction "G_G") (pintype "bidirectional"))
      (node (ref "Q54") (pin "D") (pinfunction "D_D") (pintype "bidirectional"))
    )
    (net (code "71") (name "BTN8_UP_CLR") (class "Default")
      (node (ref "Q54") (pin "G") (pinfunction "G_G") (pintype "bidirectional"))
      (node (ref "R81") (pin "2") (pinfunction "2_2") (pintype "passive"))
    )
    (net (code "72") (name "BTN8_UP_SENSE") (class "Default")
      (node (ref "Q53") (pin "D") (pinfunction "D_D") (pintype "bidirectional"))
      (node (ref "R80") (pin "1") (pinfunction "1_1") (pintype "passive"))
    )
    (net (code "73") (name "BTN9_DOWN_CAP") (class "Default")
      (node (ref "C32") (pin "1") (pinfunction "1_1") (pintype "passive"))
      (node (ref "D32") (pin "K") (pinfunction "K_K") (pintype "bidirectional"))
      (node (ref "Q63") (pin "G") (pinfunction "G_G") (pintype "bidirectional"))
      (node (ref "Q64") (pin "D") (pinfunction "D_D") (pintype "bidirectional"))
    )
    (net (code "74") (name "BTN9_DOWN_CLR") (class "Default")
      (node (ref "Q64") (pin "G") (pinfunction "G_G") (pintype "bidirectional"))
      (node (ref "R95") (pin "2") (pinfunction "2_2") (pintype "passive"))
    )
    (net (code "75") (name "BTN9_DOWN_SENSE") (class "Default")
      (node (ref "Q63") (pin "D") (pinfunction "D_D") (pintype "bidirectional"))
      (node (ref "R96") (pin "1") (pinfunction "1_1") (pintype "passive"))
    )
    (net (code "76") (name "BTN9_PIN1") (class "Default")
      (node (ref "AF16") (pin "P$1") (pinfunction "P$1_P$1") (pintype "bidirectional"))
      (node (ref "D31") (pin "A") (pinfunction "A_A") (pintype "bidirectional"))
      (node (ref "R91") (pin "2") (pinfunction "2_2") (pintype "passive"))
      (node (ref "U16") (pin "P$4") (pinfunction "P$4_P$4") (pintype "bidirectional"))
    )
    (net (code "77") (name "BTN9_PIN3") (class "Default")
      (node (ref "AF16") (pin "P$2") (pinfunction "P$2_P$2") (pintype "bidirectional"))
      (node (ref "D32") (pin "A") (pinfunction "A_A") (pintype "bidirectional"))
      (node (ref "R94") (pin "2") (pinfunction "2_2") (pintype "passive"))
      (node (ref "U16") (pin "P$3") (pinfunction "P$3_P$3") (pintype "bidirectional"))
    )
    (net (code "78") (name "BTN9_UP_CAP") (class "Default")
      (node (ref "C31") (pin "1") (pinfunction "1_1") (pintype "passive"))
      (node (ref "D31") (pin "K") (pinfunction "K_K") (pintype "bidirectional"))
      (node (ref "Q61") (pin "G") (pinfunction "G_G") (pintype "bidirectional"))
      (node (ref "Q62") (pin "D") (pinfunction "D_D") (pintype "bidirectional"))
    )
    (net (code "79") (name "BTN9_UP_CLR") (class "Default")
      (node (ref "Q62") (pin "G") (pinfunction "G_G") (pintype "bidirectional"))
      (node (ref "R93") (pin "2") (pinfunction "2_2") (pintype "passive"))
    )
    (net (code "80") (name "BTN9_UP_SENSE") (class "Default")
      (node (ref "Q61") (pin "D") (pinfunction "D_D") (pintype "bidirectional"))
      (node (ref "R92") (pin "1") (pinfunction "1_1") (pintype "passive"))
    )
    (net (code "81") (name "BTN10_DOWN_CAP") (class "Default")
      (node (ref "C36") (pin "1") (pinfunction "1_1") (pintype "passive"))
      (node (ref "D36") (pin "K") (pinfunction "K_K") (pintype "bidirectional"))
      (node (ref "Q71") (pin "G") (pinfunction "G_G") (pintype "bidirectional"))
      (node (ref "Q72") (pin "D") (pinfunction "D_D") (pintype "bidirectional"))
    )
    (net (code "82") (name "BTN10_DOWN_CLR") (class "Default")
      (node (ref "Q72") (pin "G") (pinfunction "G_G") (pintype "bidirectional"))
      (node (ref "R107") (pin "2") (pinfunction "2_2") (pintype "passive"))
    )
    (net (code "83") (name "BTN10_DOWN_SENSE") (class "Default")
      (node (ref "Q71") (pin "D") (pinfunction "D_D") (pintype "bidirectional"))
      (node (ref "R108") (pin "1") (pinfunction "1_1") (pintype "passive"))
    )
    (net (code "84") (name "BTN10_PIN1") (class "Default")
      (node (ref "AF18") (pin "P$1") (pinfunction "P$1_P$1") (pintype "bidirectional"))
      (node (ref "D35") (pin "A") (pinfunction "A_A") (pintype "bidirectional"))
      (node (ref "R103") (pin "2") (pinfunction "2_2") (pintype "passive"))
      (node (ref "U18") (pin "P$4") (pinfunction "P$4_P$4") (pintype "bidirectional"))
    )
    (net (code "85") (name "BTN10_PIN3") (class "Default")
      (node (ref "AF18") (pin "P$2") (pinfunction "P$2_P$2") (pintype "bidirectional"))
      (node (ref "D36") (pin "A") (pinfunction "A_A") (pintype "bidirectional"))
      (node (ref "R106") (pin "2") (pinfunction "2_2") (pintype "passive"))
      (node (ref "U18") (pin "P$3") (pinfunction "P$3_P$3") (pintype "bidirectional"))
    )
    (net (code "86") (name "BTN10_UP_CAP") (class "Default")
      (node (ref "C35") (pin "1") (pinfunction "1_1") (pintype "passive"))
      (node (ref "D35") (pin "K") (pinfunction "K_K") (pintype "bidirectional"))
      (node (ref "Q69") (pin "G") (pinfunction "G_G") (pintype "bidirectional"))
      (node (ref "Q70") (pin "D") (pinfunction "D_D") (pintype "bidirectional"))
    )
    (net (code "87") (name "BTN10_UP_CLR") (class "Default")
      (node (ref "Q70") (pin "G") (pinfunction "G_G") (pintype "bidirectional"))
      (node (ref "R105") (pin "2") (pinfunction "2_2") (pintype "passive"))
    )
    (net (code "88") (name "BTN10_UP_SENSE") (class "Default")
      (node (ref "Q69") (pin "D") (pinfunction "D_D") (pintype "bidirectional"))
      (node (ref "R104") (pin "1") (pinfunction "1_1") (pintype "passive"))
    )
    (net (code "89") (name "BTN11_DOWN_CAP") (class "Default")
      (node (ref "C40") (pin "1") (pinfunction "1_1") (pintype "passive"))
      (node (ref "D40") (pin "K") (pinfunction "K_K") (pintype "bidirectional"))
      (node (ref "Q79") (pin "G") (pinfunction "G_G") (pintype "bidirectional"))
      (node (ref "Q80") (pin "D") (pinfunction "D_D") (pintype "bidirectional"))
    )
    (net (code "90") (name "BTN11_DOWN_CLR") (class "Default")
      (node (ref "Q80") (pin "G") (pinfunction "G_G") (pintype "bidirectional"))
      (node (ref "R119") (pin "2") (pinfunction "2_2") (pintype "passive"))
    )
    (net (code "91") (name "BTN11_DOWN_SENSE") (class "Default")
      (node (ref "Q79") (pin "D") (pinfunction "D_D") (pintype "bidirectional"))
      (node (ref "R120") (pin "1") (pinfunction "1_1") (pintype "passive"))
    )
    (net (code "92") (name "BTN11_PIN1") (class "Default")
      (node (ref "AF20") (pin "P$1") (pinfunction "P$1_P$1") (pintype "bidirectional"))
      (node (ref "D39") (pin "A") (pinfunction "A_A") (pintype "bidirectional"))
      (node (ref "R115") (pin "2") (pinfunction "2_2") (pintype "passive"))
      (node (ref "U20") (pin "P$4") (pinfunction "P$4_P$4") (pintype "bidirectional"))
    )
    (net (code "93") (name "BTN11_PIN3") (class "Default")
      (node (ref "AF20") (pin "P$2") (pinfunction "P$2_P$2") (pintype "bidirectional"))
      (node (ref "D40") (pin "A") (pinfunction "A_A") (pintype "bidirectional"))
      (node (ref "R118") (pin "2") (pinfunction "2_2") (pintype "passive"))
      (node (ref "U20") (pin "P$3") (pinfunction "P$3_P$3") (pintype "bidirectional"))
    )
    (net (code "94") (name "BTN11_UP_CAP") (class "Default")
      (node (ref "C39") (pin "1") (pinfunction "1_1") (pintype "passive"))
      (node (ref "D39") (pin "K") (pinfunction "K_K") (pintype "bidirectional"))
      (node (ref "Q77") (pin "G") (pinfunction "G_G") (pintype "bidirectional"))
      (node (ref "Q78") (pin "D") (pinfunction "D_D") (pintype "bidirectional"))
    )
    (net (code "95") (name "BTN11_UP_CLR") (class "Default")
      (node (ref "Q78") (pin "G") (pinfunction "G_G") (pintype "bidirectional"))
      (node (ref "R117") (pin "2") (pinfunction "2_2") (pintype "passive"))
    )
    (net (code "96") (name "BTN11_UP_SENSE") (class "Default")
      (node (ref "Q77") (pin "D") (pinfunction "D_D") (pintype "bidirectional"))
      (node (ref "R116") (pin "1") (pinfunction "1_1") (pintype "passive"))
    )
    (net (code "97") (name "BTN12_DOWN_CAP") (class "Default")
      (node (ref "C14") (pin "1") (pinfunction "1_1") (pintype "passive"))
      (node (ref "D14") (pin "K") (pinfunction "K_K") (pintype "bidirectional"))
      (node (ref "Q27") (pin "G") (pinfunction "G_G") (pintype "bidirectional"))
      (node (ref "Q28") (pin "D") (pinfunction "D_D") (pintype "bidirectional"))
    )
    (net (code "98") (name "BTN12_DOWN_CLR") (class "Default")
      (node (ref "JP1") (pin "9") (pinfunction "9_9") (pintype "passive"))
      (node (ref "Q28") (pin "G") (pinfunction "G_G") (pintype "bidirectional"))
      (node (ref "R41") (pin "2") (pinfunction "2_2") (pintype "passive"))
    )
    (net (code "99") (name "BTN12_DOWN_SENSE") (class "Default")
      (node (ref "JP1") (pin "7") (pinfunction "7_7") (pintype "passive"))
      (node (ref "Q27") (pin "D") (pinfunction "D_D") (pintype "bidirectional"))
      (node (ref "R42") (pin "1") (pinfunction "1_1") (pintype "passive"))
    )
    (net (code "100") (name "BTN12_PIN1") (class "Default")
      (node (ref "AF7") (pin "P$1") (pinfunction "P$1_P$1") (pintype "bidirectional"))
      (node (ref "D13") (pin "A") (pinfunction "A_A") (pintype "bidirectional"))
      (node (ref "R37") (pin "2") (pinfunction "2_2") (pintype "passive"))
      (node (ref "U7") (pin "P$4") (pinfunction "P$4_P$4") (pintype "bidirectional"))
    )
    (net (code "101") (name "BTN12_PIN3") (class "Default")
      (node (ref "AF7") (pin "P$2") (pinfunction "P$2_P$2") (pintype "bidirectional"))
      (node (ref "D14") (pin "A") (pinfunction "A_A") (pintype "bidirectional"))
      (node (ref "R40") (pin "2") (pinfunction "2_2") (pintype "passive"))
      (node (ref "U7") (pin "P$3") (pinfunction "P$3_P$3") (pintype "bidirectional"))
    )
    (net (code "102") (name "BTN12_UP_CAP") (class "Default")
      (node (ref "C13") (pin "1") (pinfunction "1_1") (pintype "passive"))
      (node (ref "D13") (pin "K") (pinfunction "K_K") (pintype "bidirectional"))
      (node (ref "Q25") (pin "G") (pinfunction "G_G") (pintype "bidirectional"))
      (node (ref "Q26") (pin "D") (pinfunction "D_D") (pintype "bidirectional"))
    )
    (net (code "103") (name "BTN12_UP_CLR") (class "Default")
      (node (ref "JP1") (pin "5") (pinfunction "5_5") (pintype "passive"))
      (node (ref "Q26") (pin "G") (pinfunction "G_G") (pintype "bidirectional"))
      (node (ref "R39") (pin "2") (pinfunction "2_2") (pintype "passive"))
    )
    (net (code "104") (name "BTN12_UP_SENSE") (class "Default")
      (node (ref "JP1") (pin "3") (pinfunction "3_3") (pintype "passive"))
      (node (ref "Q25") (pin "D") (pinfunction "D_D") (pintype "bidirectional"))
      (node (ref "R38") (pin "1") (pinfunction "1_1") (pintype "passive"))
    )
    (net (code "105") (name "BTN13_DOWN_CAP") (class "Default")
      (node (ref "C22") (pin "1") (pinfunction "1_1") (pintype "passive"))
      (node (ref "D22") (pin "K") (pinfunction "K_K") (pintype "bidirectional"))
      (node (ref "Q43") (pin "G") (pinfunction "G_G") (pintype "bidirectional"))
      (node (ref "Q44") (pin "D") (pinfunction "D_D") (pintype "bidirectional"))
    )
    (net (code "106") (name "BTN13_DOWN_CLR") (class "Default")
      (node (ref "Q44") (pin "G") (pinfunction "G_G") (pintype "bidirectional"))
      (node (ref "R65") (pin "2") (pinfunction "2_2") (pintype "passive"))
    )
    (net (code "107") (name "BTN13_DOWN_SENSE") (class "Default")
      (node (ref "Q43") (pin "D") (pinfunction "D_D") (pintype "bidirectional"))
      (node (ref "R66") (pin "1") (pinfunction "1_1") (pintype "passive"))
    )
    (net (code "108") (name "BTN13_PIN1") (class "Default")
      (node (ref "AF11") (pin "P$1") (pinfunction "P$1_P$1") (pintype "bidirectional"))
      (node (ref "D21") (pin "A") (pinfunction "A_A") (pintype "bidirectional"))
      (node (ref "R61") (pin "2") (pinfunction "2_2") (pintype "passive"))
      (node (ref "U11") (pin "P$4") (pinfunction "P$4_P$4") (pintype "bidirectional"))
    )
    (net (code "109") (name "BTN13_PIN3") (class "Default")
      (node (ref "AF11") (pin "P$2") (pinfunction "P$2_P$2") (pintype "bidirectional"))
      (node (ref "D22") (pin "A") (pinfunction "A_A") (pintype "bidirectional"))
      (node (ref "R64") (pin "2") (pinfunction "2_2") (pintype "passive"))
      (node (ref "U11") (pin "P$3") (pinfunction "P$3_P$3") (pintype "bidirectional"))
    )
    (net (code "110") (name "BTN13_UP_CAP") (class "Default")
      (node (ref "C21") (pin "1") (pinfunction "1_1") (pintype "passive"))
      (node (ref "D21") (pin "K") (pinfunction "K_K") (pintype "bidirectional"))
      (node (ref "Q41") (pin "G") (pinfunction "G_G") (pintype "bidirectional"))
      (node (ref "Q42") (pin "D") (pinfunction "D_D") (pintype "bidirectional"))
    )
    (net (code "111") (name "BTN13_UP_CLR") (class "Default")
      (node (ref "Q42") (pin "G") (pinfunction "G_G") (pintype "bidirectional"))
      (node (ref "R63") (pin "2") (pinfunction "2_2") (pintype "passive"))
    )
    (net (code "112") (name "BTN13_UP_SENSE") (class "Default")
      (node (ref "JP1") (pin "11") (pinfunction "11_11") (pintype "passive"))
      (node (ref "Q41") (pin "D") (pinfunction "D_D") (pintype "bidirectional"))
      (node (ref "R62") (pin "1") (pinfunction "1_1") (pintype "passive"))
    )
    (net (code "113") (name "BTN14_DOWN_CAP") (class "Default")
      (node (ref "C30") (pin "1") (pinfunction "1_1") (pintype "passive"))
      (node (ref "D30") (pin "K") (pinfunction "K_K") (pintype "bidirectional"))
      (node (ref "Q59") (pin "G") (pinfunction "G_G") (pintype "bidirectional"))
      (node (ref "Q60") (pin "D") (pinfunction "D_D") (pintype "bidirectional"))
    )
    (net (code "114") (name "BTN14_DOWN_CLR") (class "Default")
      (node (ref "Q60") (pin "G") (pinfunction "G_G") (pintype "bidirectional"))
      (node (ref "R89") (pin "2") (pinfunction "2_2") (pintype "passive"))
    )
    (net (code "115") (name "BTN14_DOWN_SENSE") (class "Default")
      (node (ref "Q59") (pin "D") (pinfunction "D_D") (pintype "bidirectional"))
      (node (ref "R90") (pin "1") (pinfunction "1_1") (pintype "passive"))
    )
    (net (code "116") (name "BTN14_PIN1") (class "Default")
      (node (ref "AF15") (pin "P$1") (pinfunction "P$1_P$1") (pintype "bidirectional"))
      (node (ref "D29") (pin "A") (pinfunction "A_A") (pintype "bidirectional"))
      (node (ref "R85") (pin "2") (pinfunction "2_2") (pintype "passive"))
      (node (ref "U15") (pin "P$4") (pinfunction "P$4_P$4") (pintype "bidirectional"))
    )
    (net (code "117") (name "BTN14_PIN3") (class "Default")
      (node (ref "AF15") (pin "P$2") (pinfunction "P$2_P$2") (pintype "bidirectional"))
      (node (ref "D30") (pin "A") (pinfunction "A_A") (pintype "bidirectional"))
      (node (ref "R88") (pin "2") (pinfunction "2_2") (pintype "passive"))
      (node (ref "U15") (pin "P$3") (pinfunction "P$3_P$3") (pintype "bidirectional"))
    )
    (net (code "118") (name "BTN14_UP_CAP") (class "Default")
      (node (ref "C29") (pin "1") (pinfunction "1_1") (pintype "passive"))
      (node (ref "D29") (pin "K") (pinfunction "K_K") (pintype "bidirectional"))
      (node (ref "Q57") (pin "G") (pinfunction "G_G") (pintype "bidirectional"))
      (node (ref "Q58") (pin "D") (pinfunction "D_D") (pintype "bidirectional"))
    )
    (net (code "119") (name "BTN14_UP_CLR") (class "Default")
      (node (ref "Q58") (pin "G") (pinfunction "G_G") (pintype "bidirectional"))
      (node (ref "R87") (pin "2") (pinfunction "2_2") (pintype "passive"))
    )
    (net (code "120") (name "BTN14_UP_SENSE") (class "Default")
      (node (ref "Q57") (pin "D") (pinfunction "D_D") (pintype "bidirectional"))
      (node (ref "R86") (pin "1") (pinfunction "1_1") (pintype "passive"))
    )
    (net (code "121") (name "BTN15_DOWN_CAP") (class "Default")
      (node (ref "C38") (pin "1") (pinfunction "1_1") (pintype "passive"))
      (node (ref "D38") (pin "K") (pinfunction "K_K") (pintype "bidirectional"))
      (node (ref "Q75") (pin "G") (pinfunction "G_G") (pintype "bidirectional"))
      (node (ref "Q76") (pin "D") (pinfunction "D_D") (pintype "bidirectional"))
    )
    (net (code "122") (name "BTN15_DOWN_CLR") (class "Default")
      (node (ref "Q76") (pin "G") (pinfunction "G_G") (pintype "bidirectional"))
      (node (ref "R113") (pin "2") (pinfunction "2_2") (pintype "passive"))
    )
    (net (code "123") (name "BTN15_DOWN_SENSE") (class "Default")
      (node (ref "Q75") (pin "D") (pinfunction "D_D") (pintype "bidirectional"))
      (node (ref "R114") (pin "1") (pinfunction "1_1") (pintype "passive"))
    )
    (net (code "124") (name "BTN15_PIN1") (class "Default")
      (node (ref "AF19") (pin "P$1") (pinfunction "P$1_P$1") (pintype "bidirectional"))
      (node (ref "D37") (pin "A") (pinfunction "A_A") (pintype "bidirectional"))
      (node (ref "R109") (pin "2") (pinfunction "2_2") (pintype "passive"))
      (node (ref "U19") (pin "P$4") (pinfunction "P$4_P$4") (pintype "bidirectional"))
    )
    (net (code "125") (name "BTN15_PIN3") (class "Default")
      (node (ref "AF19") (pin "P$2") (pinfunction "P$2_P$2") (pintype "bidirectional"))
      (node (ref "D38") (pin "A") (pinfunction "A_A") (pintype "bidirectional"))
      (node (ref "R112") (pin "2") (pinfunction "2_2") (pintype "passive"))
      (node (ref "U19") (pin "P$3") (pinfunction "P$3_P$3") (pintype "bidirectional"))
    )
    (net (code "126") (name "BTN15_UP_CAP") (class "Default")
      (node (ref "C37") (pin "1") (pinfunction "1_1") (pintype "passive"))
      (node (ref "D37") (pin "K") (pinfunction "K_K") (pintype "bidirectional"))
      (node (ref "Q73") (pin "G") (pinfunction "G_G") (pintype "bidirectional"))
      (node (ref "Q74") (pin "D") (pinfunction "D_D") (pintype "bidirectional"))
    )
    (net (code "127") (name "BTN15_UP_CLR") (class "Default")
      (node (ref "Q74") (pin "G") (pinfunction "G_G") (pintype "bidirectional"))
      (node (ref "R111") (pin "2") (pinfunction "2_2") (pintype "passive"))
    )
    (net (code "128") (name "BTN15_UP_SENSE") (class "Default")
      (node (ref "Q73") (pin "D") (pinfunction "D_D") (pintype "bidirectional"))
      (node (ref "R110") (pin "1") (pinfunction "1_1") (pintype "passive"))
    )
    (net (code "129") (name "GND") (class "Default")
      (node (ref "C10") (pin "2") (pinfunction "2_2") (pintype "passive"))
      (node (ref "C11") (pin "2") (pinfunction "2_2") (pintype "passive"))
      (node (ref "C12") (pin "2") (pinfunction "2_2") (pintype "passive"))
      (node (ref "C13") (pin "2") (pinfunction "2_2") (pintype "passive"))
      (node (ref "C14") (pin "2") (pinfunction "2_2") (pintype "passive"))
      (node (ref "C15") (pin "2") (pinfunction "2_2") (pintype "passive"))
      (node (ref "C16") (pin "2") (pinfunction "2_2") (pintype "passive"))
      (node (ref "C19") (pin "2") (pinfunction "2_2") (pintype "passive"))
      (node (ref "C20") (pin "2") (pinfunction "2_2") (pintype "passive"))
      (node (ref "C21") (pin "2") (pinfunction "2_2") (pintype "passive"))
      (node (ref "C22") (pin "2") (pinfunction "2_2") (pintype "passive"))
      (node (ref "C23") (pin "2") (pinfunction "2_2") (pintype "passive"))
      (node (ref "C24") (pin "2") (pinfunction "2_2") (pintype "passive"))
      (node (ref "C27") (pin "2") (pinfunction "2_2") (pintype "passive"))
      (node (ref "C28") (pin "2") (pinfunction "2_2") (pintype "passive"))
      (node (ref "C29") (pin "2") (pinfunction "2_2") (pintype "passive"))
      (node (ref "C3") (pin "2") (pinfunction "2_2") (pintype "passive"))
      (node (ref "C30") (pin "2") (pinfunction "2_2") (pintype "passive"))
      (node (ref "C31") (pin "2") (pinfunction "2_2") (pintype "passive"))
      (node (ref "C32") (pin "2") (pinfunction "2_2") (pintype "passive"))
      (node (ref "C35") (pin "2") (pinfunction "2_2") (pintype "passive"))
      (node (ref "C36") (pin "2") (pinfunction "2_2") (pintype "passive"))
      (node (ref "C37") (pin "2") (pinfunction "2_2") (pintype "passive"))
      (node (ref "C38") (pin "2") (pinfunction "2_2") (pintype "passive"))
      (node (ref "C39") (pin "2") (pinfunction "2_2") (pintype "passive"))
      (node (ref "C4") (pin "2") (pinfunction "2_2") (pintype "passive"))
      (node (ref "C40") (pin "2") (pinfunction "2_2") (pintype "passive"))
      (node (ref "C5") (pin "2") (pinfunction "2_2") (pintype "passive"))
      (node (ref "C6") (pin "2") (pinfunction "2_2") (pintype "passive"))
      (node (ref "C7") (pin "2") (pinfunction "2_2") (pintype "passive"))
      (node (ref "C8") (pin "2") (pinfunction "2_2") (pintype "passive"))
      (node (ref "C9") (pin "2") (pinfunction "2_2") (pintype "passive"))
      (node (ref "JP1") (pin "4") (pinfunction "4_4") (pintype "passive"))
      (node (ref "Q10") (pin "S") (pinfunction "S_S") (pintype "bidirectional"))
      (node (ref "Q11") (pin "S") (pinfunction "S_S") (pintype "bidirectional"))
      (node (ref "Q12") (pin "S") (pinfunction "S_S") (pintype "bidirectional"))
      (node (ref "Q13") (pin "S") (pinfunction "S_S") (pintype "bidirectional"))
      (node (ref "Q14") (pin "S") (pinfunction "S_S") (pintype "bidirectional"))
      (node (ref "Q15") (pin "S") (pinfunction "S_S") (pintype "bidirectional"))
      (node (ref "Q16") (pin "S") (pinfunction "S_S") (pintype "bidirectional"))
      (node (ref "Q17") (pin "S") (pinfunction "S_S") (pintype "bidirectional"))
      (node (ref "Q18") (pin "S") (pinfunction "S_S") (pintype "bidirectional"))
      (node (ref "Q19") (pin "S") (pinfunction "S_S") (pintype "bidirectional"))
      (node (ref "Q20") (pin "S") (pinfunction "S_S") (pintype "bidirectional"))
      (node (ref "Q21") (pin "S") (pinfunction "S_S") (pintype "bidirectional"))
      (node (ref "Q22") (pin "S") (pinfunction "S_S") (pintype "bidirectional"))
      (node (ref "Q23") (pin "S") (pinfunction "S_S") (pintype "bidirectional"))
      (node (ref "Q24") (pin "S") (pinfunction "S_S") (pintype "bidirectional"))
      (node (ref "Q25") (pin "S") (pinfunction "S_S") (pintype "bidirectional"))
      (node (ref "Q26") (pin "S") (pinfunction "S_S") (pintype "bidirectional"))
      (node (ref "Q27") (pin "S") (pinfunction "S_S") (pintype "bidirectional"))
      (node (ref "Q28") (pin "S") (pinfunction "S_S") (pintype "bidirectional"))
      (node (ref "Q29") (pin "S") (pinfunction "S_S") (pintype "bidirectional"))
      (node (ref "Q30") (pin "S") (pinfunction "S_S") (pintype "bidirectional"))
      (node (ref "Q31") (pin "S") (pinfunction "S_S") (pintype "bidirectional"))
      (node (ref "Q32") (pin "S") (pinfunction "S_S") (pintype "bidirectional"))
      (node (ref "Q37") (pin "S") (pinfunction "S_S") (pintype "bidirectional"))
      (node (ref "Q38") (pin "S") (pinfunction "S_S") (pintype "bidirectional"))
      (node (ref "Q39") (pin "S") (pinfunction "S_S") (pintype "bidirectional"))
      (node (ref "Q40") (pin "S") (pinfunction "S_S") (pintype "bidirectional"))
      (node (ref "Q41") (pin "S") (pinfunction "S_S") (pintype "bidirectional"))
      (node (ref "Q42") (pin "S") (pinfunction "S_S") (pintype "bidirectional"))
      (node (ref "Q43") (pin "S") (pinfunction "S_S") (pintype "bidirectional"))
      (node (ref "Q44") (pin "S") (pinfunction "S_S") (pintype "bidirectional"))
      (node (ref "Q45") (pin "S") (pinfunction "S_S") (pintype "bidirectional"))
      (node (ref "Q46") (pin "S") (pinfunction "S_S") (pintype "bidirectional"))
      (node (ref "Q47") (pin "S") (pinfunction "S_S") (pintype "bidirectional"))
      (node (ref "Q48") (pin "S") (pinfunction "S_S") (pintype "bidirectional"))
      (node (ref "Q5") (pin "S") (pinfunction "S_S") (pintype "bidirectional"))
      (node (ref "Q53") (pin "S") (pinfunction "S_S") (pintype "bidirectional"))
      (node (ref "Q54") (pin "S") (pinfunction "S_S") (pintype "bidirectional"))
      (node (ref "Q55") (pin "S") (pinfunction "S_S") (pintype "bidirectional"))
      (node (ref "Q56") (pin "S") (pinfunction "S_S") (pintype "bidirectional"))
      (node (ref "Q57") (pin "S") (pinfunction "S_S") (pintype "bidirectional"))
      (node (ref "Q58") (pin "S") (pinfunction "S_S") (pintype "bidirectional"))
      (node (ref "Q59") (pin "S") (pinfunction "S_S") (pintype "bidirectional"))
      (node (ref "Q6") (pin "S") (pinfunction "S_S") (pintype "bidirectional"))
      (node (ref "Q60") (pin "S") (pinfunction "S_S") (pintype "bidirectional"))
      (node (ref "Q61") (pin "S") (pinfunction "S_S") (pintype "bidirectional"))
      (node (ref "Q62") (pin "S") (pinfunction "S_S") (pintype "bidirectional"))
      (node (ref "Q63") (pin "S") (pinfunction "S_S") (pintype "bidirectional"))
      (node (ref "Q64") (pin "S") (pinfunction "S_S") (pintype "bidirectional"))
      (node (ref "Q69") (pin "S") (pinfunction "S_S") (pintype "bidirectional"))
      (node (ref "Q7") (pin "S") (pinfunction "S_S") (pintype "bidirectional"))
      (node (ref "Q70") (pin "S") (pinfunction "S_S") (pintype "bidirectional"))
      (node (ref "Q71") (pin "S") (pinfunction "S_S") (pintype "bidirectional"))
      (node (ref "Q72") (pin "S") (pinfunction "S_S") (pintype "bidirectional"))
      (node (ref "Q73") (pin "S") (pinfunction "S_S") (pintype "bidirectional"))
      (node (ref "Q74") (pin "S") (pinfunction "S_S") (pintype "bidirectional"))
      (node (ref "Q75") (pin "S") (pinfunction "S_S") (pintype "bidirectional"))
      (node (ref "Q76") (pin "S") (pinfunction "S_S") (pintype "bidirectional"))
      (node (ref "Q77") (pin "S") (pinfunction "S_S") (pintype "bidirectional"))
      (node (ref "Q78") (pin "S") (pinfunction "S_S") (pintype "bidirectional"))
      (node (ref "Q79") (pin "S") (pinfunction "S_S") (pintype "bidirectional"))
      (node (ref "Q8") (pin "S") (pinfunction "S_S") (pintype "bidirectional"))
      (node (ref "Q80") (pin "S") (pinfunction "S_S") (pintype "bidirectional"))
      (node (ref "Q9") (pin "S") (pinfunction "S_S") (pintype "bidirectional"))
      (node (ref "R10") (pin "1") (pinfunction "1_1") (pintype "passive"))
      (node (ref "R103") (pin "1") (pinfunction "1_1") (pintype "passive"))
      (node (ref "R105") (pin "1") (pinfunction "1_1") (pintype "passive"))
      (node (ref "R106") (pin "1") (pinfunction "1_1") (pintype "passive"))
      (node (ref "R107") (pin "1") (pinfunction "1_1") (pintype "passive"))
      (node (ref "R109") (pin "1") (pinfunction "1_1") (pintype "passive"))
      (node (ref "R11") (pin "1") (pinfunction "1_1") (pintype "passive"))
      (node (ref "R111") (pin "1") (pinfunction "1_1") (pintype "passive"))
      (node (ref "R112") (pin "1") (pinfunction "1_1") (pintype "passive"))
      (node (ref "R113") (pin "1") (pinfunction "1_1") (pintype "passive"))
      (node (ref "R115") (pin "1") (pinfunction "1_1") (pintype "passive"))
      (node (ref "R117") (pin "1") (pinfunction "1_1") (pintype "passive"))
      (node (ref "R118") (pin "1") (pinfunction "1_1") (pintype "passive"))
      (node (ref "R119") (pin "1") (pinfunction "1_1") (pintype "passive"))
      (node (ref "R13") (pin "1") (pinfunction "1_1") (pintype "passive"))
      (node (ref "R15") (pin "1") (pinfunction "1_1") (pintype "passive"))
      (node (ref "R16") (pin "1") (pinfunction "1_1") (pintype "passive"))
      (node (ref "R17") (pin "1") (pinfunction "1_1") (pintype "passive"))
      (node (ref "R19") (pin "1") (pinfunction "1_1") (pintype "passive"))
      (node (ref "R21") (pin "1") (pinfunction "1_1") (pintype "passive"))
      (node (ref "R22") (pin "1") (pinfunction "1_1") (pintype "passive"))
      (node (ref "R23") (pin "1") (pinfunction "1_1") (pintype "passive"))
      (node (ref "R25") (pin "1") (pinfunction "1_1") (pintype "passive"))
      (node (ref "R27") (pin "1") (pinfunction "1_1") (pintype "passive"))
      (node (ref "R28") (pin "1") (pinfunction "1_1") (pintype "passive"))
      (node (ref "R29") (pin "1") (pinfunction "1_1") (pintype "passive"))
      (node (ref "R31") (pin "1") (pinfunction "1_1") (pintype "passive"))
      (node (ref "R33") (pin "1") (pinfunction "1_1") (pintype "passive"))
      (node (ref "R34") (pin "1") (pinfunction "1_1") (pintype "passive"))
      (node (ref "R35") (pin "1") (pinfunction "1_1") (pintype "passive"))
      (node (ref "R37") (pin "1") (pinfunction "1_1") (pintype "passive"))
      (node (ref "R39") (pin "1") (pinfunction "1_1") (pintype "passive"))
      (node (ref "R40") (pin "1") (pinfunction "1_1") (pintype "passive"))
      (node (ref "R41") (pin "1") (pinfunction "1_1") (pintype "passive"))
      (node (ref "R43") (pin "1") (pinfunction "1_1") (pintype "passive"))
      (node (ref "R45") (pin "1") (pinfunction "1_1") (pintype "passive"))
      (node (ref "R46") (pin "1") (pinfunction "1_1") (pintype "passive"))
      (node (ref "R47") (pin "1") (pinfunction "1_1") (pintype "passive"))
      (node (ref "R55") (pin "1") (pinfunction "1_1") (pintype "passive"))
      (node (ref "R57") (pin "1") (pinfunction "1_1") (pintype "passive"))
      (node (ref "R58") (pin "1") (pinfunction "1_1") (pintype "passive"))
      (node (ref "R59") (pin "1") (pinfunction "1_1") (pintype "passive"))
      (node (ref "R61") (pin "1") (pinfunction "1_1") (pintype "passive"))
      (node (ref "R63") (pin "1") (pinfunction "1_1") (pintype "passive"))
      (node (ref "R64") (pin "1") (pinfunction "1_1") (pintype "passive"))
      (node (ref "R65") (pin "1") (pinfunction "1_1") (pintype "passive"))
      (node (ref "R67") (pin "1") (pinfunction "1_1") (pintype "passive"))
      (node (ref "R69") (pin "1") (pinfunction "1_1") (pintype "passive"))
      (node (ref "R7") (pin "1") (pinfunction "1_1") (pintype "passive"))
      (node (ref "R70") (pin "1") (pinfunction "1_1") (pintype "passive"))
      (node (ref "R71") (pin "1") (pinfunction "1_1") (pintype "passive"))
      (node (ref "R79") (pin "1") (pinfunction "1_1") (pintype "passive"))
      (node (ref "R81") (pin "1") (pinfunction "1_1") (pintype "passive"))
      (node (ref "R82") (pin "1") (pinfunction "1_1") (pintype "passive"))
      (node (ref "R83") (pin "1") (pinfunction "1_1") (pintype "passive"))
      (node (ref "R85") (pin "1") (pinfunction "1_1") (pintype "passive"))
      (node (ref "R87") (pin "1") (pinfunction "1_1") (pintype "passive"))
      (node (ref "R88") (pin "1") (pinfunction "1_1") (pintype "passive"))
      (node (ref "R89") (pin "1") (pinfunction "1_1") (pintype "passive"))
      (node (ref "R9") (pin "1") (pinfunction "1_1") (pintype "passive"))
      (node (ref "R91") (pin "1") (pinfunction "1_1") (pintype "passive"))
      (node (ref "R93") (pin "1") (pinfunction "1_1") (pintype "passive"))
      (node (ref "R94") (pin "1") (pinfunction "1_1") (pintype "passive"))
      (node (ref "R95") (pin "1") (pinfunction "1_1") (pintype "passive"))
      (node (ref "U10") (pin "P$2") (pinfunction "P$2_P$2") (pintype "bidirectional"))
      (node (ref "U11") (pin "P$2") (pinfunction "P$2_P$2") (pintype "bidirectional"))
      (node (ref "U12") (pin "P$2") (pinfunction "P$2_P$2") (pintype "bidirectional"))
      (node (ref "U14") (pin "P$2") (pinfunction "P$2_P$2") (pintype "bidirectional"))
      (node (ref "U15") (pin "P$2") (pinfunction "P$2_P$2") (pintype "bidirectional"))
      (node (ref "U16") (pin "P$2") (pinfunction "P$2_P$2") (pintype "bidirectional"))
      (node (ref "U18") (pin "P$2") (pinfunction "P$2_P$2") (pintype "bidirectional"))
      (node (ref "U19") (pin "P$2") (pinfunction "P$2_P$2") (pintype "bidirectional"))
      (node (ref "U2") (pin "P$2") (pinfunction "P$2_P$2") (pintype "bidirectional"))
      (node (ref "U20") (pin "P$2") (pinfunction "P$2_P$2") (pintype "bidirectional"))
      (node (ref "U3") (pin "P$2") (pinfunction "P$2_P$2") (pintype "bidirectional"))
      (node (ref "U4") (pin "P$2") (pinfunction "P$2_P$2") (pintype "bidirectional"))
      (node (ref "U5") (pin "P$2") (pinfunction "P$2_P$2") (pintype "bidirectional"))
      (node (ref "U6") (pin "P$2") (pinfunction "P$2_P$2") (pintype "bidirectional"))
      (node (ref "U7") (pin "P$2") (pinfunction "P$2_P$2") (pintype "bidirectional"))
      (node (ref "U8") (pin "P$2") (pinfunction "P$2_P$2") (pintype "bidirectional"))
    )
    (net (code "130") (name "HARVEST") (class "Default")
      (node (ref "U10") (pin "P$1") (pinfunction "P$1_P$1") (pintype "bidirectional"))
      (node (ref "U11") (pin "P$1") (pinfunction "P$1_P$1") (pintype "bidirectional"))
      (node (ref "U12") (pin "P$1") (pinfunction "P$1_P$1") (pintype "bidirectional"))
      (node (ref "U14") (pin "P$1") (pinfunction "P$1_P$1") (pintype "bidirectional"))
      (node (ref "U15") (pin "P$1") (pinfunction "P$1_P$1") (pintype "bidirectional"))
      (node (ref "U16") (pin "P$1") (pinfunction "P$1_P$1") (pintype "bidirectional"))
      (node (ref "U18") (pin "P$1") (pinfunction "P$1_P$1") (pintype "bidirectional"))
      (node (ref "U19") (pin "P$1") (pinfunction "P$1_P$1") (pintype "bidirectional"))
      (node (ref "U2") (pin "P$1") (pinfunction "P$1_P$1") (pintype "bidirectional"))
      (node (ref "U20") (pin "P$1") (pinfunction "P$1_P$1") (pintype "bidirectional"))
      (node (ref "U3") (pin "P$1") (pinfunction "P$1_P$1") (pintype "bidirectional"))
      (node (ref "U4") (pin "P$1") (pinfunction "P$1_P$1") (pintype "bidirectional"))
      (node (ref "U5") (pin "P$1") (pinfunction "P$1_P$1") (pintype "bidirectional"))
      (node (ref "U6") (pin "P$1") (pinfunction "P$1_P$1") (pintype "bidirectional"))
      (node (ref "U7") (pin "P$1") (pinfunction "P$1_P$1") (pintype "bidirectional"))
      (node (ref "U8") (pin "P$1") (pinfunction "P$1_P$1") (pintype "bidirectional"))
    )
    (net (code "131") (name "VCC") (class "Default")
      (node (ref "JP1") (pin "1") (pinfunction "1_1") (pintype "passive"))
      (node (ref "R104") (pin "2") (pinfunction "2_2") (pintype "passive"))
      (node (ref "R108") (pin "2") (pinfunction "2_2") (pintype "passive"))
      (node (ref "R110") (pin "2") (pinfunction "2_2") (pintype "passive"))
      (node (ref "R114") (pin "2") (pinfunction "2_2") (pintype "passive"))
      (node (ref "R116") (pin "2") (pinfunction "2_2") (pintype "passive"))
      (node (ref "R12") (pin "2") (pinfunction "2_2") (pintype "passive"))
      (node (ref "R120") (pin "2") (pinfunction "2_2") (pintype "passive"))
      (node (ref "R14") (pin "2") (pinfunction "2_2") (pintype "passive"))
      (node (ref "R18") (pin "2") (pinfunction "2_2") (pintype "passive"))
      (node (ref "R20") (pin "2") (pinfunction "2_2") (pintype "passive"))
      (node (ref "R24") (pin "2") (pinfunction "2_2") (pintype "passive"))
      (node (ref "R26") (pin "2") (pinfunction "2_2") (pintype "passive"))
      (node (ref "R30") (pin "2") (pinfunction "2_2") (pintype "passive"))
      (node (ref "R32") (pin "2") (pinfunction "2_2") (pintype "passive"))
      (node (ref "R36") (pin "2") (pinfunction "2_2") (pintype "passive"))
      (node (ref "R38") (pin "2") (pinfunction "2_2") (pintype "passive"))
      (node (ref "R42") (pin "2") (pinfunction "2_2") (pintype "passive"))
      (node (ref "R44") (pin "2") (pinfunction "2_2") (pintype "passive"))
      (node (ref "R48") (pin "2") (pinfunction "2_2") (pintype "passive"))
      (node (ref "R56") (pin "2") (pinfunction "2_2") (pintype "passive"))
      (node (ref "R60") (pin "2") (pinfunction "2_2") (pintype "passive"))
      (node (ref "R62") (pin "2") (pinfunction "2_2") (pintype "passive"))
      (node (ref "R66") (pin "2") (pinfunction "2_2") (pintype "passive"))
      (node (ref "R68") (pin "2") (pinfunction "2_2") (pintype "passive"))
      (node (ref "R72") (pin "2") (pinfunction "2_2") (pintype "passive"))
      (node (ref "R8") (pin "2") (pinfunction "2_2") (pintype "passive"))
      (node (ref "R80") (pin "2") (pinfunction "2_2") (pintype "passive"))
      (node (ref "R84") (pin "2") (pinfunction "2_2") (pintype "passive"))
      (node (ref "R86") (pin "2") (pinfunction "2_2") (pintype "passive"))
      (node (ref "R90") (pin "2") (pinfunction "2_2") (pintype "passive"))
      (node (ref "R92") (pin "2") (pinfunction "2_2") (pintype "passive"))
      (node (ref "R96") (pin "2") (pinfunction "2_2") (pintype "passive"))
    )
    (net (code "132") (name "unconnected-(JP1-Pad2)") (class "Default")
      (node (ref "JP1") (pin "2") (pinfunction "2_2") (pintype "passive"))
    )
    (net (code "133") (name "unconnected-(JP1-Pad6)") (class "Default")
      (node (ref "JP1") (pin "6") (pinfunction "6_6") (pintype "passive"))
    )
    (net (code "134") (name "unconnected-(JP1-Pad8)") (class "Default")
      (node (ref "JP1") (pin "8") (pinfunction "8_8") (pintype "passive"))
    )
    (net (code "135") (name "unconnected-(JP1-Pad10)") (class "Default")
      (node (ref "JP1") (pin "10") (pinfunction "10_10") (pintype "passive"))
    )
    (net (code "136") (name "unconnected-(JP1-Pad12)") (class "Default")
      (node (ref "JP1") (pin "12") (pinfunction "12_12") (pintype "passive"))
    )
    (net (code "137") (name "unconnected-(JP1-Pad13)") (class "Default")
      (node (ref "JP1") (pin "13") (pinfunction "13_13") (pintype "passive"))
    )
    (net (code "138") (name "unconnected-(JP1-Pad14)") (class "Default")
      (node (ref "JP1") (pin "14") (pinfunction "14_14") (pintype "passive"))
    )
    (net (code "139") (name "unconnected-(JP1-Pad15)") (class "Default")
      (node (ref "JP1") (pin "15") (pinfunction "15_15") (pintype "passive"))
    )
    (net (code "140") (name "unconnected-(JP1-Pad16)") (class "Default")
      (node (ref "JP1") (pin "16") (pinfunction "16_16") (pintype "passive"))
    )
    (net (code "141") (name "unconnected-(JP1-Pad17)") (class "Default")
      (node (ref "JP1") (pin "17") (pinfunction "17_17") (pintype "passive"))
    )
    (net (code "142") (name "unconnected-(JP1-Pad18)") (class "Default")
      (node (ref "JP1") (pin "18") (pinfunction "18_18") (pintype "passive"))
    )
    (net (code "143") (name "unconnected-(JP1-Pad19)") (class "Default")
      (node (ref "JP1") (pin "19") (pinfunction "19_19") (pintype "passive"))
    )
    (net (code "144") (name "unconnected-(JP1-Pad20)") (class "Default")
      (node (ref "JP1") (pin "20") (pinfunction "20_20") (pintype "passive"))
    )
    (net (code "145") (name "unconnected-(JP2-Pad1)") (class "Default")
      (node (ref "JP2") (pin "1") (pinfunction "1_1") (pintype "passive"))
    )
    (net (code "146") (name "unconnected-(JP2-Pad2)") (class "Default")
      (node (ref "JP2") (pin "2") (pinfunction "2_2") (pintype "passive"))
    )
    (net (code "147") (name "unconnected-(JP2-Pad3)") (class "Default")
      (node (ref "JP2") (pin "3") (pinfunction "3_3") (pintype "passive"))
    )
    (net (code "148") (name "unconnected-(JP2-Pad4)") (class "Default")
      (node (ref "JP2") (pin "4") (pinfunction "4_4") (pintype "passive"))
    )
    (net (code "149") (name "unconnected-(JP2-Pad5)") (class "Default")
      (node (ref "JP2") (pin "5") (pinfunction "5_5") (pintype "passive"))
    )
    (net (code "150") (name "unconnected-(JP2-Pad6)") (class "Default")
      (node (ref "JP2") (pin "6") (pinfunction "6_6") (pintype "passive"))
    )
    (net (code "151") (name "unconnected-(JP2-Pad7)") (class "Default")
      (node (ref "JP2") (pin "7") (pinfunction "7_7") (pintype "passive"))
    )
    (net (code "152") (name "unconnected-(JP2-Pad8)") (class "Default")
      (node (ref "JP2") (pin "8") (pinfunction "8_8") (pintype "passive"))
    )
    (net (code "153") (name "unconnected-(JP2-Pad9)") (class "Default")
      (node (ref "JP2") (pin "9") (pinfunction "9_9") (pintype "passive"))
    )
    (net (code "154") (name "unconnected-(JP2-Pad10)") (class "Default")
      (node (ref "JP2") (pin "10") (pinfunction "10_10") (pintype "passive"))
    )
    (net (code "155") (name "unconnected-(JP2-Pad11)") (class "Default")
      (node (ref "JP2") (pin "11") (pinfunction "11_11") (pintype "passive"))
    )
    (net (code "156") (name "unconnected-(JP2-Pad12)") (class "Default")
      (node (ref "JP2") (pin "12") (pinfunction "12_12") (pintype "passive"))
    )
    (net (code "157") (name "unconnected-(JP2-Pad13)") (class "Default")
      (node (ref "JP2") (pin "13") (pinfunction "13_13") (pintype "passive"))
    )
    (net (code "158") (name "unconnected-(JP2-Pad14)") (class "Default")
      (node (ref "JP2") (pin "14") (pinfunction "14_14") (pintype "passive"))
    )
    (net (code "159") (name "unconnected-(JP2-Pad15)") (class "Default")
      (node (ref "JP2") (pin "15") (pinfunction "15_15") (pintype "passive"))
    )
    (net (code "160") (name "unconnected-(JP2-Pad16)") (class "Default")
      (node (ref "JP2") (pin "16") (pinfunction "16_16") (pintype "passive"))
    )
    (net (code "161") (name "unconnected-(JP2-Pad17)") (class "Default")
      (node (ref "JP2") (pin "17") (pinfunction "17_17") (pintype "passive"))
    )
    (net (code "162") (name "unconnected-(JP2-Pad18)") (class "Default")
      (node (ref "JP2") (pin "18") (pinfunction "18_18") (pintype "passive"))
    )
    (net (code "163") (name "unconnected-(JP2-Pad19)") (class "Default")
      (node (ref "JP2") (pin "19") (pinfunction "19_19") (pintype "passive"))
    )
    (net (code "164") (name "unconnected-(JP2-Pad20)") (class "Default")
      (node (ref "JP2") (pin "20") (pinfunction "20_20") (pintype "passive"))
    )
  )
)
